# rat.net
KiCad netlist of a schematic drawn in EAGLE
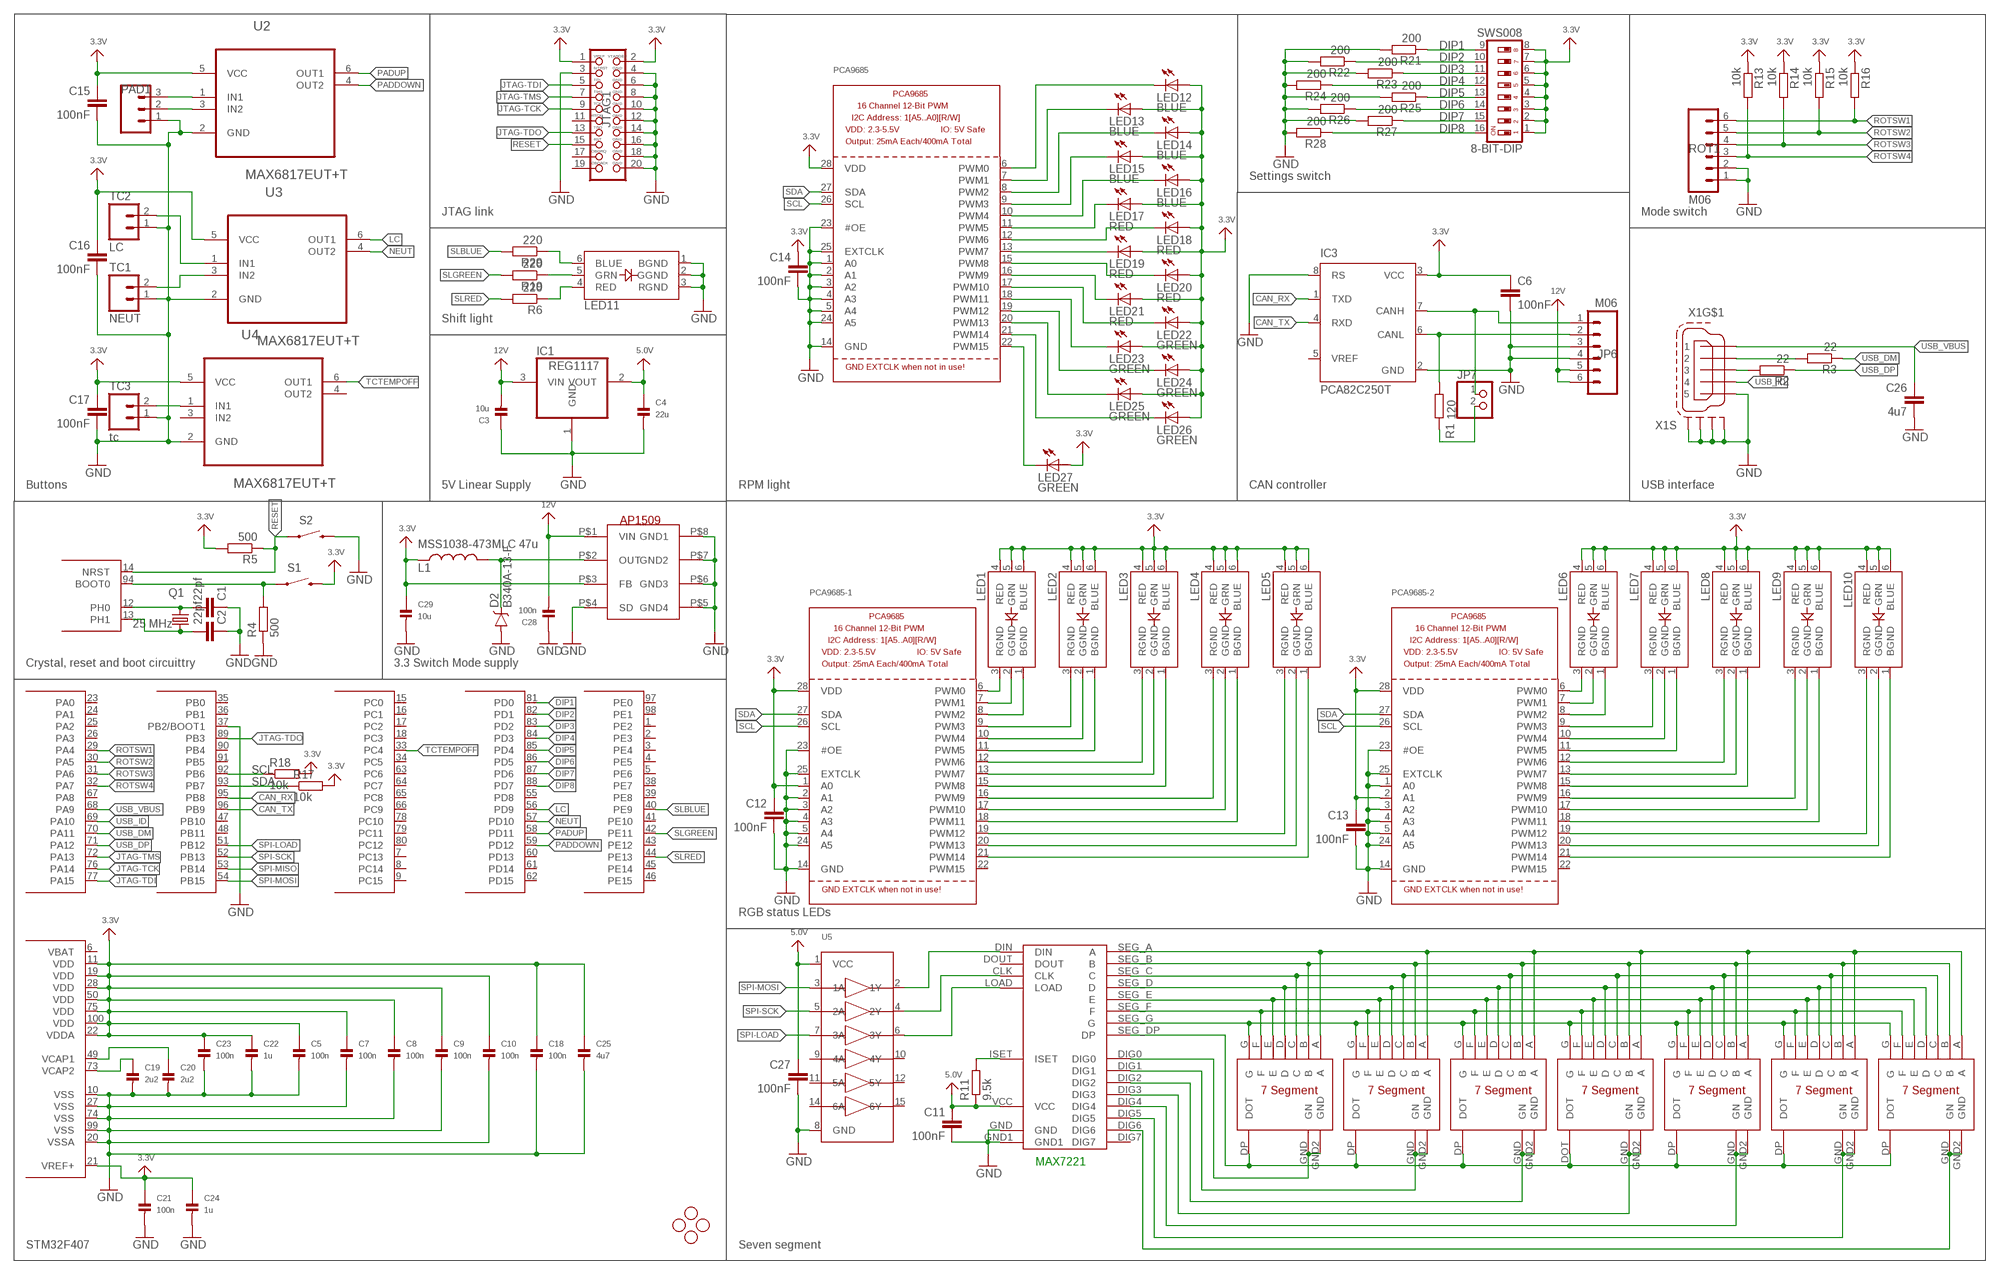
[diagram p0: schematic, sheet 1]

(export (version "E")
  (design (tool "Eeschema 10.0.6"))
  (components
    (comp (ref "8-BIT-DIP")
      (value "SWS008")
      (footprint "eagle-import:SMS-008")
      (libsource (lib "eagle-import") (part "SWS008"))
    )
    (comp (ref "C1")
      (value "22pf")
      (footprint "eagle-import:C0603K")
      (libsource (lib "eagle-import") (part "C-EUC0603K"))
    )
    (comp (ref "C2")
      (value "22pf")
      (footprint "eagle-import:C0603K")
      (libsource (lib "eagle-import") (part "C-EUC0603K"))
    )
    (comp (ref "C3")
      (value "10u")
      (footprint "eagle-import:0805")
      (libsource (lib "eagle-import") (part "CAP_CERAMIC0805"))
    )
    (comp (ref "C4")
      (value "22u")
      (footprint "eagle-import:_0603MP")
      (libsource (lib "eagle-import") (part "CAP_CERAMIC_0603MP"))
    )
    (comp (ref "C5")
      (value "100n")
      (footprint "eagle-import:_0402MP")
      (libsource (lib "eagle-import") (part "CAP_CERAMIC_0402MP"))
    )
    (comp (ref "C6")
      (value "100nF")
      (footprint "eagle-import:C0603K")
      (libsource (lib "eagle-import") (part "C-EUC0603K"))
    )
    (comp (ref "C7")
      (value "100n")
      (footprint "eagle-import:_0402MP")
      (libsource (lib "eagle-import") (part "CAP_CERAMIC_0402MP"))
    )
    (comp (ref "C8")
      (value "100n")
      (footprint "eagle-import:_0402MP")
      (libsource (lib "eagle-import") (part "CAP_CERAMIC_0402MP"))
    )
    (comp (ref "C9")
      (value "100n")
      (footprint "eagle-import:_0402MP")
      (libsource (lib "eagle-import") (part "CAP_CERAMIC_0402MP"))
    )
    (comp (ref "C10")
      (value "100n")
      (footprint "eagle-import:_0402MP")
      (libsource (lib "eagle-import") (part "CAP_CERAMIC_0402MP"))
    )
    (comp (ref "C11")
      (value "100nF")
      (footprint "eagle-import:C0603K")
      (libsource (lib "eagle-import") (part "C-EUC0603K"))
    )
    (comp (ref "C12")
      (value "100nF")
      (footprint "eagle-import:C0603K")
      (libsource (lib "eagle-import") (part "C-EUC0603K"))
    )
    (comp (ref "C13")
      (value "100nF")
      (footprint "eagle-import:C0603K")
      (libsource (lib "eagle-import") (part "C-EUC0603K"))
    )
    (comp (ref "C14")
      (value "100nF")
      (footprint "eagle-import:C0603K")
      (libsource (lib "eagle-import") (part "C-EUC0603K"))
    )
    (comp (ref "C15")
      (value "100nF")
      (footprint "eagle-import:C0603K")
      (libsource (lib "eagle-import") (part "C-EUC0603K"))
    )
    (comp (ref "C16")
      (value "100nF")
      (footprint "eagle-import:C0603K")
      (libsource (lib "eagle-import") (part "C-EUC0603K"))
    )
    (comp (ref "C17")
      (value "100nF")
      (footprint "eagle-import:C0603K")
      (libsource (lib "eagle-import") (part "C-EUC0603K"))
    )
    (comp (ref "C18")
      (value "100n")
      (footprint "eagle-import:_0402MP")
      (libsource (lib "eagle-import") (part "CAP_CERAMIC_0402MP"))
    )
    (comp (ref "C19")
      (value "2u2")
      (footprint "eagle-import:_0402MP")
      (libsource (lib "eagle-import") (part "CAP_CERAMIC_0402MP"))
    )
    (comp (ref "C20")
      (value "2u2")
      (footprint "eagle-import:_0402MP")
      (libsource (lib "eagle-import") (part "CAP_CERAMIC_0402MP"))
    )
    (comp (ref "C21")
      (value "100n")
      (footprint "eagle-import:_0402MP")
      (libsource (lib "eagle-import") (part "CAP_CERAMIC_0402MP"))
    )
    (comp (ref "C22")
      (value "1u")
      (footprint "eagle-import:_0402MP")
      (libsource (lib "eagle-import") (part "CAP_CERAMIC_0402MP"))
    )
    (comp (ref "C23")
      (value "100n")
      (footprint "eagle-import:_0402MP")
      (libsource (lib "eagle-import") (part "CAP_CERAMIC_0402MP"))
    )
    (comp (ref "C24")
      (value "1u")
      (footprint "eagle-import:_0402MP")
      (libsource (lib "eagle-import") (part "CAP_CERAMIC_0402MP"))
    )
    (comp (ref "C25")
      (value "4u7")
      (footprint "eagle-import:_0402MP")
      (libsource (lib "eagle-import") (part "CAP_CERAMIC_0402MP"))
    )
    (comp (ref "C26")
      (value "4u7")
      (footprint "eagle-import:C0603K")
      (libsource (lib "eagle-import") (part "C-EUC0603K"))
    )
    (comp (ref "C27")
      (value "100nF")
      (footprint "eagle-import:C0603K")
      (libsource (lib "eagle-import") (part "C-EUC0603K"))
    )
    (comp (ref "C28")
      (value "100n")
      (footprint "eagle-import:_0603MP")
      (libsource (lib "eagle-import") (part "CAP_CERAMIC_0603MP"))
    )
    (comp (ref "C29")
      (value "10u")
      (footprint "eagle-import:0805")
      (libsource (lib "eagle-import") (part "CAP_CERAMIC0805"))
    )
    (comp (ref "D2")
      (value "B340A-13-F")
      (footprint "eagle-import:SMA-DIODE")
      (libsource (lib "eagle-import") (part "MBRA140"))
    )
    (comp (ref "IC1")
      (value "REG1117")
      (footprint "eagle-import:SOT223")
      (libsource (lib "eagle-import") (part "REG1117"))
    )
    (comp (ref "IC3")
      (value "PCA82C250T")
      (footprint "eagle-import:SO8")
      (libsource (lib "eagle-import") (part "PCA82C250T"))
    )
    (comp (ref "JP2")
      (value "STAND-OFF")
      (footprint "eagle-import:STAND-OFF")
      (libsource (lib "eagle-import") (part "STAND-OFF"))
    )
    (comp (ref "JP3")
      (value "STAND-OFF")
      (footprint "eagle-import:STAND-OFF")
      (libsource (lib "eagle-import") (part "STAND-OFF"))
    )
    (comp (ref "JP4")
      (value "STAND-OFF")
      (footprint "eagle-import:STAND-OFF")
      (libsource (lib "eagle-import") (part "STAND-OFF"))
    )
    (comp (ref "JP5")
      (value "STAND-OFF")
      (footprint "eagle-import:STAND-OFF")
      (libsource (lib "eagle-import") (part "STAND-OFF"))
    )
    (comp (ref "JP6")
      (value "M06")
      (footprint "eagle-import:S6B_PH")
      (libsource (lib "eagle-import") (part "M06"))
    )
    (comp (ref "JP7")
      (value "PINHD-1X2/90")
      (footprint "eagle-import:1X02_90")
      (libsource (lib "eagle-import") (part "PINHD-1X2/90"))
    )
    (comp (ref "JTAG1")
      (value "JTAG-ARMEDGE")
      (footprint "eagle-import:MOLEX20_RIGHTANGLE")
      (libsource (lib "eagle-import") (part "JTAG-ARMEDGE"))
    )
    (comp (ref "L1")
      (value "MSS1038-473MLC 47u")
      (footprint "eagle-import:CDRH125")
      (libsource (lib "eagle-import") (part "INDUCTORPWR"))
    )
    (comp (ref "LED1")
      (value "LED_RGB_PLCC6CREE-CLV6A")
      (footprint "eagle-import:RGBLED_PLCC6")
      (libsource (lib "eagle-import") (part "LED_RGB_PLCC6CREE-CLV6A"))
    )
    (comp (ref "LED2")
      (value "LED_RGB_PLCC6CREE-CLV6A")
      (footprint "eagle-import:RGBLED_PLCC6")
      (libsource (lib "eagle-import") (part "LED_RGB_PLCC6CREE-CLV6A"))
    )
    (comp (ref "LED3")
      (value "LED_RGB_PLCC6CREE-CLV6A")
      (footprint "eagle-import:RGBLED_PLCC6")
      (libsource (lib "eagle-import") (part "LED_RGB_PLCC6CREE-CLV6A"))
    )
    (comp (ref "LED4")
      (value "LED_RGB_PLCC6CREE-CLV6A")
      (footprint "eagle-import:RGBLED_PLCC6")
      (libsource (lib "eagle-import") (part "LED_RGB_PLCC6CREE-CLV6A"))
    )
    (comp (ref "LED5")
      (value "LED_RGB_PLCC6CREE-CLV6A")
      (footprint "eagle-import:RGBLED_PLCC6")
      (libsource (lib "eagle-import") (part "LED_RGB_PLCC6CREE-CLV6A"))
    )
    (comp (ref "LED6")
      (value "LED_RGB_PLCC6CREE-CLV6A")
      (footprint "eagle-import:RGBLED_PLCC6")
      (libsource (lib "eagle-import") (part "LED_RGB_PLCC6CREE-CLV6A"))
    )
    (comp (ref "LED7")
      (value "LED_RGB_PLCC6CREE-CLV6A")
      (footprint "eagle-import:RGBLED_PLCC6")
      (libsource (lib "eagle-import") (part "LED_RGB_PLCC6CREE-CLV6A"))
    )
    (comp (ref "LED8")
      (value "LED_RGB_PLCC6CREE-CLV6A")
      (footprint "eagle-import:RGBLED_PLCC6")
      (libsource (lib "eagle-import") (part "LED_RGB_PLCC6CREE-CLV6A"))
    )
    (comp (ref "LED9")
      (value "LED_RGB_PLCC6CREE-CLV6A")
      (footprint "eagle-import:RGBLED_PLCC6")
      (libsource (lib "eagle-import") (part "LED_RGB_PLCC6CREE-CLV6A"))
    )
    (comp (ref "LED10")
      (value "LED_RGB_PLCC6CREE-CLV6A")
      (footprint "eagle-import:RGBLED_PLCC6")
      (libsource (lib "eagle-import") (part "LED_RGB_PLCC6CREE-CLV6A"))
    )
    (comp (ref "LED11")
      (value "LED_RGB_PLCC6CREE-CLV6A")
      (footprint "eagle-import:RGBLED_PLCC6")
      (libsource (lib "eagle-import") (part "LED_RGB_PLCC6CREE-CLV6A"))
    )
    (comp (ref "LED12")
      (value "BLUE")
      (footprint "eagle-import:1206")
      (libsource (lib "eagle-import") (part "LEDSMT1206"))
    )
    (comp (ref "LED13")
      (value "BLUE")
      (footprint "eagle-import:1206")
      (libsource (lib "eagle-import") (part "LEDSMT1206"))
    )
    (comp (ref "LED14")
      (value "BLUE")
      (footprint "eagle-import:1206")
      (libsource (lib "eagle-import") (part "LEDSMT1206"))
    )
    (comp (ref "LED15")
      (value "BLUE")
      (footprint "eagle-import:1206")
      (libsource (lib "eagle-import") (part "LEDSMT1206"))
    )
    (comp (ref "LED16")
      (value "BLUE")
      (footprint "eagle-import:1206")
      (libsource (lib "eagle-import") (part "LEDSMT1206"))
    )
    (comp (ref "LED17")
      (value "RED")
      (footprint "eagle-import:1206")
      (libsource (lib "eagle-import") (part "LEDSMT1206"))
    )
    (comp (ref "LED18")
      (value "RED")
      (footprint "eagle-import:1206")
      (libsource (lib "eagle-import") (part "LEDSMT1206"))
    )
    (comp (ref "LED19")
      (value "RED")
      (footprint "eagle-import:1206")
      (libsource (lib "eagle-import") (part "LEDSMT1206"))
    )
    (comp (ref "LED20")
      (value "RED")
      (footprint "eagle-import:1206")
      (libsource (lib "eagle-import") (part "LEDSMT1206"))
    )
    (comp (ref "LED21")
      (value "RED")
      (footprint "eagle-import:1206")
      (libsource (lib "eagle-import") (part "LEDSMT1206"))
    )
    (comp (ref "LED22")
      (value "GREEN")
      (footprint "eagle-import:1206")
      (libsource (lib "eagle-import") (part "LEDSMT1206"))
    )
    (comp (ref "LED23")
      (value "GREEN")
      (footprint "eagle-import:1206")
      (libsource (lib "eagle-import") (part "LEDSMT1206"))
    )
    (comp (ref "LED24")
      (value "GREEN")
      (footprint "eagle-import:1206")
      (libsource (lib "eagle-import") (part "LEDSMT1206"))
    )
    (comp (ref "LED25")
      (value "GREEN")
      (footprint "eagle-import:1206")
      (libsource (lib "eagle-import") (part "LEDSMT1206"))
    )
    (comp (ref "LED26")
      (value "GREEN")
      (footprint "eagle-import:1206")
      (libsource (lib "eagle-import") (part "LEDSMT1206"))
    )
    (comp (ref "LED27")
      (value "GREEN")
      (footprint "eagle-import:1206")
      (libsource (lib "eagle-import") (part "LEDSMT1206"))
    )
    (comp (ref "MAX7221")
      (value "MAX7221-SMD")
      (footprint "eagle-import:MAX7221")
      (libsource (lib "eagle-import") (part "MAX7221-SMD"))
    )
    (comp (ref "PAD1")
      (value "M03")
      (footprint "eagle-import:S3B-PH")
      (libsource (lib "eagle-import") (part "M03"))
    )
    (comp (ref "PCA9685")
      (value "PCA9685")
      (footprint "eagle-import:TSSOP28")
      (libsource (lib "eagle-import") (part "PCA9685"))
    )
    (comp (ref "PCA9685-1")
      (value "PCA9685")
      (footprint "eagle-import:TSSOP28")
      (libsource (lib "eagle-import") (part "PCA9685"))
    )
    (comp (ref "PCA9685-2")
      (value "PCA9685")
      (footprint "eagle-import:TSSOP28")
      (libsource (lib "eagle-import") (part "PCA9685"))
    )
    (comp (ref "Q1")
      (value "25 MHz")
      (footprint "eagle-import:HC49U70")
      (libsource (lib "eagle-import") (part "CRYSTALHC49U70"))
    )
    (comp (ref "R1")
      (value "120")
      (footprint "eagle-import:R0603")
      (libsource (lib "eagle-import") (part "resistor_R-EU_R0603"))
    )
    (comp (ref "R2")
      (value "22")
      (footprint "eagle-import:R0603")
      (libsource (lib "eagle-import") (part "R-EU_R0603"))
    )
    (comp (ref "R3")
      (value "22")
      (footprint "eagle-import:R0603")
      (libsource (lib "eagle-import") (part "R-EU_R0603"))
    )
    (comp (ref "R4")
      (value "500")
      (footprint "eagle-import:R0603")
      (libsource (lib "eagle-import") (part "R-EU_R0603"))
    )
    (comp (ref "R5")
      (value "500")
      (footprint "eagle-import:R0603")
      (libsource (lib "eagle-import") (part "R-EU_R0603"))
    )
    (comp (ref "R6")
      (value "220")
      (footprint "eagle-import:R0603")
      (libsource (lib "eagle-import") (part "R-EU_R0603"))
    )
    (comp (ref "R11")
      (value "9.5k")
      (footprint "eagle-import:R0603")
      (libsource (lib "eagle-import") (part "R-EU_R0603"))
    )
    (comp (ref "R13")
      (value "10k")
      (footprint "eagle-import:R0603")
      (libsource (lib "eagle-import") (part "R-EU_R0603"))
    )
    (comp (ref "R14")
      (value "10k")
      (footprint "eagle-import:R0603")
      (libsource (lib "eagle-import") (part "R-EU_R0603"))
    )
    (comp (ref "R15")
      (value "10k")
      (footprint "eagle-import:R0603")
      (libsource (lib "eagle-import") (part "R-EU_R0603"))
    )
    (comp (ref "R16")
      (value "10k")
      (footprint "eagle-import:R0603")
      (libsource (lib "eagle-import") (part "R-EU_R0603"))
    )
    (comp (ref "R17")
      (value "10k")
      (footprint "eagle-import:R0603")
      (libsource (lib "eagle-import") (part "R-EU_R0603"))
    )
    (comp (ref "R18")
      (value "10k")
      (footprint "eagle-import:R0603")
      (libsource (lib "eagle-import") (part "R-EU_R0603"))
    )
    (comp (ref "R19")
      (value "220")
      (footprint "eagle-import:R0603")
      (libsource (lib "eagle-import") (part "R-EU_R0603"))
    )
    (comp (ref "R21")
      (value "200")
      (footprint "eagle-import:R0603")
      (libsource (lib "eagle-import") (part "R-EU_R0603"))
    )
    (comp (ref "R22")
      (value "200")
      (footprint "eagle-import:R0603")
      (libsource (lib "eagle-import") (part "R-EU_R0603"))
    )
    (comp (ref "R23")
      (value "200")
      (footprint "eagle-import:R0603")
      (libsource (lib "eagle-import") (part "R-EU_R0603"))
    )
    (comp (ref "R24")
      (value "200")
      (footprint "eagle-import:R0603")
      (libsource (lib "eagle-import") (part "R-EU_R0603"))
    )
    (comp (ref "R25")
      (value "200")
      (footprint "eagle-import:R0603")
      (libsource (lib "eagle-import") (part "R-EU_R0603"))
    )
    (comp (ref "R26")
      (value "200")
      (footprint "eagle-import:R0603")
      (libsource (lib "eagle-import") (part "R-EU_R0603"))
    )
    (comp (ref "R27")
      (value "200")
      (footprint "eagle-import:R0603")
      (libsource (lib "eagle-import") (part "R-EU_R0603"))
    )
    (comp (ref "R28")
      (value "200")
      (footprint "eagle-import:R0603")
      (libsource (lib "eagle-import") (part "R-EU_R0603"))
    )
    (comp (ref "R29")
      (value "220")
      (footprint "eagle-import:R0603")
      (libsource (lib "eagle-import") (part "R-EU_R0603"))
    )
    (comp (ref "ROT1")
      (value "M06")
      (footprint "eagle-import:S6B_PH")
      (libsource (lib "eagle-import") (part "M06"))
    )
    (comp (ref "S1")
      (value "SWITCH-MOMENTARY-2-SMD-1101NE")
      (footprint "eagle-import:TACTILE-SWITCH-1101NE")
      (libsource (lib "eagle-import") (part "SWITCH-MOMENTARY-2-SMD-1101NE"))
    )
    (comp (ref "S2")
      (value "SWITCH-MOMENTARY-2-SMD-1101NE")
      (footprint "eagle-import:TACTILE-SWITCH-1101NE")
      (libsource (lib "eagle-import") (part "SWITCH-MOMENTARY-2-SMD-1101NE"))
    )
    (comp (ref "TC1")
      (value "NEUT")
      (footprint "eagle-import:S2B-PH")
      (libsource (lib "eagle-import") (part "M02-JST-2MM-SMT"))
    )
    (comp (ref "TC2")
      (value "LC")
      (footprint "eagle-import:S2B-PH")
      (libsource (lib "eagle-import") (part "M02-JST-2MM-SMT"))
    )
    (comp (ref "TC3")
      (value "tc")
      (footprint "eagle-import:S2B-PH")
      (libsource (lib "eagle-import") (part "M02-JST-2MM-SMT"))
    )
    (comp (ref "U$2")
      (value "REDSEVENSEGMENT")
      (footprint "eagle-import:REDSEGMENT")
      (libsource (lib "eagle-import") (part "REDSEVENSEGMENT"))
    )
    (comp (ref "U$3")
      (value "REDSEVENSEGMENT")
      (footprint "eagle-import:REDSEGMENT")
      (libsource (lib "eagle-import") (part "REDSEVENSEGMENT"))
    )
    (comp (ref "U$4")
      (value "REDSEVENSEGMENT")
      (footprint "eagle-import:REDSEGMENT")
      (libsource (lib "eagle-import") (part "REDSEVENSEGMENT"))
    )
    (comp (ref "U$5")
      (value "BIGSEVENSEGMENT")
      (footprint "eagle-import:BIGSEVENSEGMENT")
      (libsource (lib "eagle-import") (part "BIGSEVENSEGMENT"))
    )
    (comp (ref "U$6")
      (value "REDSEVENSEGMENT")
      (footprint "eagle-import:REDSEGMENT")
      (libsource (lib "eagle-import") (part "REDSEVENSEGMENT"))
    )
    (comp (ref "U$7")
      (value "REDSEVENSEGMENT")
      (footprint "eagle-import:REDSEGMENT")
      (libsource (lib "eagle-import") (part "REDSEVENSEGMENT"))
    )
    (comp (ref "U$8")
      (value "REDSEVENSEGMENT")
      (footprint "eagle-import:REDSEGMENT")
      (libsource (lib "eagle-import") (part "REDSEVENSEGMENT"))
    )
    (comp (ref "U$10")
      (value "AP1509")
      (footprint "eagle-import:SOP-8L")
      (libsource (lib "eagle-import") (part "AP1509"))
    )
    (comp (ref "U1")
      (value "STM32F4-100")
      (footprint "eagle-import:SQFP-S-14X14-100")
      (libsource (lib "eagle-import") (part "STM32F4-100"))
    )
    (comp (ref "U2")
      (value "MAX6817EUT+T")
      (footprint "eagle-import:SOT95P280X145-6N")
      (libsource (lib "eagle-import") (part "MAX6817EUT+T"))
    )
    (comp (ref "U3")
      (value "MAX6817EUT+T")
      (footprint "eagle-import:SOT95P280X145-6N")
      (libsource (lib "eagle-import") (part "MAX6817EUT+T"))
    )
    (comp (ref "U4")
      (value "MAX6817EUT+T")
      (footprint "eagle-import:SOT95P280X145-6N")
      (libsource (lib "eagle-import") (part "MAX6817EUT+T"))
    )
    (comp (ref "U5")
      (value "74HC4050D")
      (footprint "eagle-import:SOIC16")
      (libsource (lib "eagle-import") (part "74HC4050D"))
    )
    (comp (ref "X1")
      (value "MINI-USB-SCHIELD-32005-201")
      (footprint "eagle-import:32005-201")
      (libsource (lib "eagle-import") (part "MINI-USB-SCHIELD-32005-201"))
    )
  )
  (nets
    (net (code "1") (name "/VBAT") (class "Default")
      (node (ref "U1") (pin "6") (pinfunction "VBAT_6") (pintype "power_in"))
    )
    (net (code "2") (name "3.3V") (class "Default")
      (node (ref "8-BIT-DIP") (pin "1") (pinfunction "1_1") (pintype "passive"))
      (node (ref "8-BIT-DIP") (pin "2") (pinfunction "2_2") (pintype "passive"))
      (node (ref "8-BIT-DIP") (pin "3") (pinfunction "3_3") (pintype "passive"))
      (node (ref "8-BIT-DIP") (pin "4") (pinfunction "4_4") (pintype "passive"))
      (node (ref "8-BIT-DIP") (pin "5") (pinfunction "5_5") (pintype "passive"))
      (node (ref "8-BIT-DIP") (pin "6") (pinfunction "6_6") (pintype "passive"))
      (node (ref "8-BIT-DIP") (pin "7") (pinfunction "7_7") (pintype "passive"))
      (node (ref "8-BIT-DIP") (pin "8") (pinfunction "8_8") (pintype "passive"))
      (node (ref "C10") (pin "1") (pinfunction "P$1_1") (pintype "passive"))
      (node (ref "C12") (pin "1") (pinfunction "1_1") (pintype "passive"))
      (node (ref "C13") (pin "1") (pinfunction "1_1") (pintype "passive"))
      (node (ref "C14") (pin "1") (pinfunction "1_1") (pintype "passive"))
      (node (ref "C15") (pin "1") (pinfunction "1_1") (pintype "passive"))
      (node (ref "C16") (pin "1") (pinfunction "1_1") (pintype "passive"))
      (node (ref "C17") (pin "1") (pinfunction "1_1") (pintype "passive"))
      (node (ref "C18") (pin "1") (pinfunction "P$1_1") (pintype "passive"))
      (node (ref "C21") (pin "1") (pinfunction "P$1_1") (pintype "passive"))
      (node (ref "C22") (pin "1") (pinfunction "P$1_1") (pintype "passive"))
      (node (ref "C23") (pin "1") (pinfunction "P$1_1") (pintype "passive"))
      (node (ref "C24") (pin "1") (pinfunction "P$1_1") (pintype "passive"))
      (node (ref "C25") (pin "1") (pinfunction "P$1_1") (pintype "passive"))
      (node (ref "C29") (pin "1") (pinfunction "P$1_1") (pintype "passive"))
      (node (ref "C5") (pin "1") (pinfunction "P$1_1") (pintype "passive"))
      (node (ref "C6") (pin "1") (pinfunction "1_1") (pintype "passive"))
      (node (ref "C7") (pin "1") (pinfunction "P$1_1") (pintype "passive"))
      (node (ref "C8") (pin "1") (pinfunction "P$1_1") (pintype "passive"))
      (node (ref "C9") (pin "1") (pinfunction "P$1_1") (pintype "passive"))
      (node (ref "IC3") (pin "3") (pinfunction "VCC_3") (pintype "power_in"))
      (node (ref "JTAG1") (pin "1") (pinfunction "1_1") (pintype "passive"))
      (node (ref "JTAG1") (pin "2") (pinfunction "2_2") (pintype "passive"))
      (node (ref "L1") (pin "1") (pinfunction "1_1") (pintype "passive"))
      (node (ref "LED1") (pin "4") (pinfunction "RED_4") (pintype "bidirectional"))
      (node (ref "LED1") (pin "5") (pinfunction "GRN_5") (pintype "bidirectional"))
      (node (ref "LED1") (pin "6") (pinfunction "BLUE_6") (pintype "bidirectional"))
      (node (ref "LED10") (pin "4") (pinfunction "RED_4") (pintype "bidirectional"))
      (node (ref "LED10") (pin "5") (pinfunction "GRN_5") (pintype "bidirectional"))
      (node (ref "LED10") (pin "6") (pinfunction "BLUE_6") (pintype "bidirectional"))
      (node (ref "LED12") (pin "A") (pinfunction "A_A") (pintype "passive"))
      (node (ref "LED13") (pin "A") (pinfunction "A_A") (pintype "passive"))
      (node (ref "LED14") (pin "A") (pinfunction "A_A") (pintype "passive"))
      (node (ref "LED15") (pin "A") (pinfunction "A_A") (pintype "passive"))
      (node (ref "LED16") (pin "A") (pinfunction "A_A") (pintype "passive"))
      (node (ref "LED17") (pin "A") (pinfunction "A_A") (pintype "passive"))
      (node (ref "LED18") (pin "A") (pinfunction "A_A") (pintype "passive"))
      (node (ref "LED19") (pin "A") (pinfunction "A_A") (pintype "passive"))
      (node (ref "LED2") (pin "4") (pinfunction "RED_4") (pintype "bidirectional"))
      (node (ref "LED2") (pin "5") (pinfunction "GRN_5") (pintype "bidirectional"))
      (node (ref "LED2") (pin "6") (pinfunction "BLUE_6") (pintype "bidirectional"))
      (node (ref "LED20") (pin "A") (pinfunction "A_A") (pintype "passive"))
      (node (ref "LED21") (pin "A") (pinfunction "A_A") (pintype "passive"))
      (node (ref "LED22") (pin "A") (pinfunction "A_A") (pintype "passive"))
      (node (ref "LED23") (pin "A") (pinfunction "A_A") (pintype "passive"))
      (node (ref "LED24") (pin "A") (pinfunction "A_A") (pintype "passive"))
      (node (ref "LED25") (pin "A") (pinfunction "A_A") (pintype "passive"))
      (node (ref "LED26") (pin "A") (pinfunction "A_A") (pintype "passive"))
      (node (ref "LED27") (pin "A") (pinfunction "A_A") (pintype "passive"))
      (node (ref "LED3") (pin "4") (pinfunction "RED_4") (pintype "bidirectional"))
      (node (ref "LED3") (pin "5") (pinfunction "GRN_5") (pintype "bidirectional"))
      (node (ref "LED3") (pin "6") (pinfunction "BLUE_6") (pintype "bidirectional"))
      (node (ref "LED4") (pin "4") (pinfunction "RED_4") (pintype "bidirectional"))
      (node (ref "LED4") (pin "5") (pinfunction "GRN_5") (pintype "bidirectional"))
      (node (ref "LED4") (pin "6") (pinfunction "BLUE_6") (pintype "bidirectional"))
      (node (ref "LED5") (pin "4") (pinfunction "RED_4") (pintype "bidirectional"))
      (node (ref "LED5") (pin "5") (pinfunction "GRN_5") (pintype "bidirectional"))
      (node (ref "LED5") (pin "6") (pinfunction "BLUE_6") (pintype "bidirectional"))
      (node (ref "LED6") (pin "4") (pinfunction "RED_4") (pintype "bidirectional"))
      (node (ref "LED6") (pin "5") (pinfunction "GRN_5") (pintype "bidirectional"))
      (node (ref "LED6") (pin "6") (pinfunction "BLUE_6") (pintype "bidirectional"))
      (node (ref "LED7") (pin "4") (pinfunction "RED_4") (pintype "bidirectional"))
      (node (ref "LED7") (pin "5") (pinfunction "GRN_5") (pintype "bidirectional"))
      (node (ref "LED7") (pin "6") (pinfunction "BLUE_6") (pintype "bidirectional"))
      (node (ref "LED8") (pin "4") (pinfunction "RED_4") (pintype "bidirectional"))
      (node (ref "LED8") (pin "5") (pinfunction "GRN_5") (pintype "bidirectional"))
      (node (ref "LED8") (pin "6") (pinfunction "BLUE_6") (pintype "bidirectional"))
      (node (ref "LED9") (pin "4") (pinfunction "RED_4") (pintype "bidirectional"))
      (node (ref "LED9") (pin "5") (pinfunction "GRN_5") (pintype "bidirectional"))
      (node (ref "LED9") (pin "6") (pinfunction "BLUE_6") (pintype "bidirectional"))
      (node (ref "PCA9685") (pin "28") (pinfunction "VDD_28") (pintype "power_in"))
      (node (ref "PCA9685-1") (pin "1") (pinfunction "A0_1") (pintype "bidirectional"))
      (node (ref "PCA9685-1") (pin "28") (pinfunction "VDD_28") (pintype "power_in"))
      (node (ref "PCA9685-2") (pin "2") (pinfunction "A1_2") (pintype "bidirectional"))
      (node (ref "PCA9685-2") (pin "28") (pinfunction "VDD_28") (pintype "power_in"))
      (node (ref "R13") (pin "1") (pinfunction "1_1") (pintype "passive"))
      (node (ref "R14") (pin "1") (pinfunction "1_1") (pintype "passive"))
      (node (ref "R15") (pin "1") (pinfunction "1_1") (pintype "passive"))
      (node (ref "R16") (pin "1") (pinfunction "1_1") (pintype "passive"))
      (node (ref "R17") (pin "2") (pinfunction "2_2") (pintype "passive"))
      (node (ref "R18") (pin "2") (pinfunction "2_2") (pintype "passive"))
      (node (ref "R5") (pin "2") (pinfunction "2_2") (pintype "passive"))
      (node (ref "S1") (pin "P$2") (pinfunction "2_P$2") (pintype "passive"))
      (node (ref "U$10") (pin "P$3") (pinfunction "FB_P$3") (pintype "bidirectional"))
      (node (ref "U1") (pin "100") (pinfunction "VDD_100") (pintype "power_in"))
      (node (ref "U1") (pin "11") (pinfunction "VDD_11") (pintype "power_in"))
      (node (ref "U1") (pin "19") (pinfunction "VDD_19") (pintype "power_in"))
      (node (ref "U1") (pin "21") (pinfunction "VREF+_21") (pintype "passive"))
      (node (ref "U1") (pin "22") (pinfunction "VDDA_22") (pintype "power_in"))
      (node (ref "U1") (pin "28") (pinfunction "VDD_28") (pintype "power_in"))
      (node (ref "U1") (pin "50") (pinfunction "VDD_50") (pintype "power_in"))
      (node (ref "U1") (pin "75") (pinfunction "VDD_75") (pintype "power_in"))
      (node (ref "U2") (pin "5") (pinfunction "VCC_5") (pintype "power_in"))
      (node (ref "U3") (pin "5") (pinfunction "VCC_5") (pintype "power_in"))
      (node (ref "U4") (pin "5") (pinfunction "VCC_5") (pintype "power_in"))
    )
    (net (code "3") (name "5.0V") (class "Default")
      (node (ref "C11") (pin "1") (pinfunction "1_1") (pintype "passive"))
      (node (ref "C27") (pin "1") (pinfunction "1_1") (pintype "passive"))
      (node (ref "C4") (pin "1") (pinfunction "P$1_1") (pintype "passive"))
      (node (ref "IC1") (pin "2") (pinfunction "VOUT_2") (pintype "output"))
      (node (ref "MAX7221") (pin "VCC") (pinfunction "VCC_VCC") (pintype "bidirectional"))
      (node (ref "R11") (pin "1") (pinfunction "1_1") (pintype "passive"))
      (node (ref "U5") (pin "1") (pinfunction "VCC_1") (pintype "bidirectional"))
    )
    (net (code "4") (name "12V") (class "Default")
      (node (ref "C28") (pin "2") (pinfunction "P$2_2") (pintype "passive"))
      (node (ref "C3") (pin "2") (pinfunction "P$2_2") (pintype "passive"))
      (node (ref "IC1") (pin "3") (pinfunction "VIN_3") (pintype "input"))
      (node (ref "JP6") (pin "5") (pinfunction "5_5") (pintype "passive"))
      (node (ref "JP6") (pin "6") (pinfunction "6_6") (pintype "passive"))
      (node (ref "U$10") (pin "P$1") (pinfunction "VIN_P$1") (pintype "bidirectional"))
    )
    (net (code "5") (name "CAN_RX") (class "Default")
      (node (ref "IC3") (pin "1") (pinfunction "TXD_1") (pintype "input"))
      (node (ref "U1") (pin "95") (pinfunction "PB8_95") (pintype "bidirectional"))
    )
    (net (code "6") (name "CAN_TX") (class "Default")
      (node (ref "IC3") (pin "4") (pinfunction "RXD_4") (pintype "output"))
      (node (ref "U1") (pin "96") (pinfunction "PB9_96") (pintype "bidirectional"))
    )
    (net (code "7") (name "DIP1") (class "Default")
      (node (ref "8-BIT-DIP") (pin "9") (pinfunction "9_9") (pintype "passive"))
      (node (ref "R21") (pin "1") (pinfunction "1_1") (pintype "passive"))
      (node (ref "U1") (pin "81") (pinfunction "PD0_81") (pintype "bidirectional"))
    )
    (net (code "8") (name "DIP2") (class "Default")
      (node (ref "8-BIT-DIP") (pin "10") (pinfunction "10_10") (pintype "passive"))
      (node (ref "R22") (pin "1") (pinfunction "1_1") (pintype "passive"))
      (node (ref "U1") (pin "82") (pinfunction "PD1_82") (pintype "bidirectional"))
    )
    (net (code "9") (name "DIP3") (class "Default")
      (node (ref "8-BIT-DIP") (pin "11") (pinfunction "11_11") (pintype "passive"))
      (node (ref "R23") (pin "1") (pinfunction "1_1") (pintype "passive"))
      (node (ref "U1") (pin "83") (pinfunction "PD2_83") (pintype "bidirectional"))
    )
    (net (code "10") (name "DIP4") (class "Default")
      (node (ref "8-BIT-DIP") (pin "12") (pinfunction "12_12") (pintype "passive"))
      (node (ref "R24") (pin "1") (pinfunction "1_1") (pintype "passive"))
      (node (ref "U1") (pin "84") (pinfunction "PD3_84") (pintype "bidirectional"))
    )
    (net (code "11") (name "DIP5") (class "Default")
      (node (ref "8-BIT-DIP") (pin "13") (pinfunction "13_13") (pintype "passive"))
      (node (ref "R25") (pin "1") (pinfunction "1_1") (pintype "passive"))
      (node (ref "U1") (pin "85") (pinfunction "PD4_85") (pintype "bidirectional"))
    )
    (net (code "12") (name "DIP6") (class "Default")
      (node (ref "8-BIT-DIP") (pin "14") (pinfunction "14_14") (pintype "passive"))
      (node (ref "R26") (pin "1") (pinfunction "1_1") (pintype "passive"))
      (node (ref "U1") (pin "86") (pinfunction "PD5_86") (pintype "bidirectional"))
    )
    (net (code "13") (name "DIP7") (class "Default")
      (node (ref "8-BIT-DIP") (pin "15") (pinfunction "15_15") (pintype "passive"))
      (node (ref "R27") (pin "1") (pinfunction "1_1") (pintype "passive"))
      (node (ref "U1") (pin "87") (pinfunction "PD6_87") (pintype "bidirectional"))
    )
    (net (code "14") (name "DIP8") (class "Default")
      (node (ref "8-BIT-DIP") (pin "16") (pinfunction "16_16") (pintype "passive"))
      (node (ref "R28") (pin "1") (pinfunction "1_1") (pintype "passive"))
      (node (ref "U1") (pin "88") (pinfunction "PD7_88") (pintype "bidirectional"))
    )
    (net (code "15") (name "GND") (class "Default")
      (node (ref "C1") (pin "1") (pinfunction "1_1") (pintype "passive"))
      (node (ref "C10") (pin "2") (pinfunction "P$2_2") (pintype "passive"))
      (node (ref "C11") (pin "2") (pinfunction "2_2") (pintype "passive"))
      (node (ref "C12") (pin "2") (pinfunction "2_2") (pintype "passive"))
      (node (ref "C13") (pin "2") (pinfunction "2_2") (pintype "passive"))
      (node (ref "C14") (pin "2") (pinfunction "2_2") (pintype "passive"))
      (node (ref "C15") (pin "2") (pinfunction "2_2") (pintype "passive"))
      (node (ref "C16") (pin "2") (pinfunction "2_2") (pintype "passive"))
      (node (ref "C17") (pin "2") (pinfunction "2_2") (pintype "passive"))
      (node (ref "C18") (pin "2") (pinfunction "P$2_2") (pintype "passive"))
      (node (ref "C19") (pin "2") (pinfunction "P$2_2") (pintype "passive"))
      (node (ref "C2") (pin "1") (pinfunction "1_1") (pintype "passive"))
      (node (ref "C20") (pin "2") (pinfunction "P$2_2") (pintype "passive"))
      (node (ref "C21") (pin "2") (pinfunction "P$2_2") (pintype "passive"))
      (node (ref "C22") (pin "2") (pinfunction "P$2_2") (pintype "passive"))
      (node (ref "C23") (pin "2") (pinfunction "P$2_2") (pintype "passive"))
      (node (ref "C24") (pin "2") (pinfunction "P$2_2") (pintype "passive"))
      (node (ref "C25") (pin "2") (pinfunction "P$2_2") (pintype "passive"))
      (node (ref "C26") (pin "2") (pinfunction "2_2") (pintype "passive"))
      (node (ref "C27") (pin "2") (pinfunction "2_2") (pintype "passive"))
      (node (ref "C28") (pin "1") (pinfunction "P$1_1") (pintype "passive"))
      (node (ref "C29") (pin "2") (pinfunction "P$2_2") (pintype "passive"))
      (node (ref "C3") (pin "1") (pinfunction "P$1_1") (pintype "passive"))
      (node (ref "C4") (pin "2") (pinfunction "P$2_2") (pintype "passive"))
      (node (ref "C5") (pin "2") (pinfunction "P$2_2") (pintype "passive"))
      (node (ref "C6") (pin "2") (pinfunction "2_2") (pintype "passive"))
      (node (ref "C7") (pin "2") (pinfunction "P$2_2") (pintype "passive"))
      (node (ref "C8") (pin "2") (pinfunction "P$2_2") (pintype "passive"))
      (node (ref "C9") (pin "2") (pinfunction "P$2_2") (pintype "passive"))
      (node (ref "D2") (pin "A") (pinfunction "A_A") (pintype "passive"))
      (node (ref "IC1") (pin "1") (pinfunction "GND_1") (pintype "power_in"))
      (node (ref "IC3") (pin "2") (pinfunction "GND_2") (pintype "power_in"))
      (node (ref "IC3") (pin "8") (pinfunction "RS_8") (pintype "input"))
      (node (ref "JP6") (pin "3") (pinfunction "3_3") (pintype "passive"))
      (node (ref "JP6") (pin "4") (pinfunction "4_4") (pintype "passive"))
      (node (ref "JTAG1") (pin "10") (pinfunction "10_10") (pintype "passive"))
      (node (ref "JTAG1") (pin "12") (pinfunction "12_12") (pintype "passive"))
      (node (ref "JTAG1") (pin "14") (pinfunction "14_14") (pintype "passive"))
      (node (ref "JTAG1") (pin "16") (pinfunction "16_16") (pintype "passive"))
      (node (ref "JTAG1") (pin "18") (pinfunction "18_18") (pintype "passive"))
      (node (ref "JTAG1") (pin "20") (pinfunction "20_20") (pintype "passive"))
      (node (ref "JTAG1") (pin "3") (pinfunction "3_3") (pintype "passive"))
      (node (ref "JTAG1") (pin "4") (pinfunction "4_4") (pintype "passive"))
      (node (ref "JTAG1") (pin "6") (pinfunction "6_6") (pintype "passive"))
      (node (ref "JTAG1") (pin "8") (pinfunction "8_8") (pintype "passive"))
      (node (ref "LED11") (pin "1") (pinfunction "BGND_1") (pintype "power_in"))
      (node (ref "LED11") (pin "2") (pinfunction "GGND_2") (pintype "power_in"))
      (node (ref "LED11") (pin "3") (pinfunction "RGND_3") (pintype "power_in"))
      (node (ref "MAX7221") (pin "GND") (pinfunction "GND_GND") (pintype "bidirectional"))
      (node (ref "MAX7221") (pin "GND1") (pinfunction "GND1_GND1") (pintype "bidirectional"))
      (node (ref "PAD1") (pin "1") (pinfunction "1_1") (pintype "passive"))
      (node (ref "PCA9685") (pin "1") (pinfunction "A0_1") (pintype "bidirectional"))
      (node (ref "PCA9685") (pin "14") (pinfunction "GND_14") (pintype "power_in"))
      (node (ref "PCA9685") (pin "2") (pinfunction "A1_2") (pintype "bidirectional"))
      (node (ref "PCA9685") (pin "23") (pinfunction "#OE_23") (pintype "input"))
      (node (ref "PCA9685") (pin "24") (pinfunction "A5_24") (pintype "bidirectional"))
      (node (ref "PCA9685") (pin "25") (pinfunction "EXTCLK_25") (pintype "input"))
      (node (ref "PCA9685") (pin "3") (pinfunction "A2_3") (pintype "bidirectional"))
      (node (ref "PCA9685") (pin "4") (pinfunction "A3_4") (pintype "bidirectional"))
      (node (ref "PCA9685") (pin "5") (pinfunction "A4_5") (pintype "bidirectional"))
      (node (ref "PCA9685-1") (pin "14") (pinfunction "GND_14") (pintype "power_in"))
      (node (ref "PCA9685-1") (pin "2") (pinfunction "A1_2") (pintype "bidirectional"))
      (node (ref "PCA9685-1") (pin "23") (pinfunction "#OE_23") (pintype "input"))
      (node (ref "PCA9685-1") (pin "24") (pinfunction "A5_24") (pintype "bidirectional"))
      (node (ref "PCA9685-1") (pin "25") (pinfunction "EXTCLK_25") (pintype "input"))
      (node (ref "PCA9685-1") (pin "3") (pinfunction "A2_3") (pintype "bidirectional"))
      (node (ref "PCA9685-1") (pin "4") (pinfunction "A3_4") (pintype "bidirectional"))
      (node (ref "PCA9685-1") (pin "5") (pinfunction "A4_5") (pintype "bidirectional"))
      (node (ref "PCA9685-2") (pin "1") (pinfunction "A0_1") (pintype "bidirectional"))
      (node (ref "PCA9685-2") (pin "14") (pinfunction "GND_14") (pintype "power_in"))
      (node (ref "PCA9685-2") (pin "23") (pinfunction "#OE_23") (pintype "input"))
      (node (ref "PCA9685-2") (pin "24") (pinfunction "A5_24") (pintype "bidirectional"))
      (node (ref "PCA9685-2") (pin "25") (pinfunction "EXTCLK_25") (pintype "input"))
      (node (ref "PCA9685-2") (pin "3") (pinfunction "A2_3") (pintype "bidirectional"))
      (node (ref "PCA9685-2") (pin "4") (pinfunction "A3_4") (pintype "bidirectional"))
      (node (ref "PCA9685-2") (pin "5") (pinfunction "A4_5") (pintype "bidirectional"))
      (node (ref "R21") (pin "2") (pinfunction "2_2") (pintype "passive"))
      (node (ref "R22") (pin "2") (pinfunction "2_2") (pintype "passive"))
      (node (ref "R23") (pin "2") (pinfunction "2_2") (pintype "passive"))
      (node (ref "R24") (pin "2") (pinfunction "2_2") (pintype "passive"))
      (node (ref "R25") (pin "2") (pinfunction "2_2") (pintype "passive"))
      (node (ref "R26") (pin "2") (pinfunction "2_2") (pintype "passive"))
      (node (ref "R27") (pin "2") (pinfunction "2_2") (pintype "passive"))
      (node (ref "R28") (pin "2") (pinfunction "2_2") (pintype "passive"))
      (node (ref "R4") (pin "1") (pinfunction "1_1") (pintype "passive"))
      (node (ref "ROT1") (pin "1") (pinfunction "1_1") (pintype "passive"))
      (node (ref "ROT1") (pin "2") (pinfunction "2_2") (pintype "passive"))
      (node (ref "S2") (pin "P$2") (pinfunction "2_P$2") (pintype "passive"))
      (node (ref "TC1") (pin "1") (pinfunction "1_1") (pintype "passive"))
      (node (ref "TC2") (pin "1") (pinfunction "1_1") (pintype "passive"))
      (node (ref "TC3") (pin "1") (pinfunction "1_1") (pintype "passive"))
      (node (ref "U$10") (pin "P$4") (pinfunction "SD_P$4") (pintype "bidirectional"))
      (node (ref "U$10") (pin "P$5") (pinfunction "GND4_P$5") (pintype "bidirectional"))
      (node (ref "U$10") (pin "P$6") (pinfunction "GND3_P$6") (pintype "bidirectional"))
      (node (ref "U$10") (pin "P$7") (pinfunction "GND2_P$7") (pintype "bidirectional"))
      (node (ref "U$10") (pin "P$8") (pinfunction "GND1_P$8") (pintype "bidirectional"))
      (node (ref "U1") (pin "10") (pinfunction "VSS_10") (pintype "power_in"))
      (node (ref "U1") (pin "20") (pinfunction "VSSA_20") (pintype "power_in"))
      (node (ref "U1") (pin "27") (pinfunction "VSS_27") (pintype "power_in"))
      (node (ref "U1") (pin "37") (pinfunction "PB2/BOOT1_37") (pintype "bidirectional"))
      (node (ref "U1") (pin "74") (pinfunction "VSS_74") (pintype "power_in"))
      (node (ref "U1") (pin "99") (pinfunction "VSS_99") (pintype "power_in"))
      (node (ref "U2") (pin "2") (pinfunction "GND_2") (pintype "passive"))
      (node (ref "U3") (pin "2") (pinfunction "GND_2") (pintype "passive"))
      (node (ref "U4") (pin "2") (pinfunction "GND_2") (pintype "passive"))
      (node (ref "U5") (pin "8") (pinfunction "GND_8") (pintype "bidirectional"))
      (node (ref "X1") (pin "5") (pinfunction "5_5") (pintype "passive"))
      (node (ref "X1") (pin "M1") (pinfunction "S1_M1") (pintype "passive"))
      (node (ref "X1") (pin "M2") (pinfunction "S2_M2") (pintype "passive"))
      (node (ref "X1") (pin "M3") (pinfunction "S3_M3") (pintype "passive"))
      (node (ref "X1") (pin "M4") (pinfunction "S4_M4") (pintype "passive"))
    )
    (net (code "16") (name "JTAG-TCK") (class "Default")
      (node (ref "JTAG1") (pin "9") (pinfunction "9_9") (pintype "passive"))
      (node (ref "U1") (pin "76") (pinfunction "PA14_76") (pintype "bidirectional"))
    )
    (net (code "17") (name "JTAG-TDI") (class "Default")
      (node (ref "JTAG1") (pin "5") (pinfunction "5_5") (pintype "passive"))
      (node (ref "U1") (pin "77") (pinfunction "PA15_77") (pintype "bidirectional"))
    )
    (net (code "18") (name "JTAG-TDO") (class "Default")
      (node (ref "JTAG1") (pin "13") (pinfunction "13_13") (pintype "passive"))
      (node (ref "U1") (pin "89") (pinfunction "PB3_89") (pintype "bidirectional"))
    )
    (net (code "19") (name "JTAG-TMS") (class "Default")
      (node (ref "JTAG1") (pin "7") (pinfunction "7_7") (pintype "passive"))
      (node (ref "U1") (pin "72") (pinfunction "PA13_72") (pintype "bidirectional"))
    )
    (net (code "20") (name "LC") (class "Default")
      (node (ref "U1") (pin "56") (pinfunction "PD9_56") (pintype "bidirectional"))
      (node (ref "U3") (pin "6") (pinfunction "OUT1_6") (pintype "output"))
    )
    (net (code "21") (name "NEUT") (class "Default")
      (node (ref "U1") (pin "57") (pinfunction "PD10_57") (pintype "bidirectional"))
      (node (ref "U3") (pin "4") (pinfunction "OUT2_4") (pintype "output"))
    )
    (net (code "22") (name "Net-(C19-P$1)") (class "Default")
      (node (ref "C19") (pin "1") (pinfunction "P$1_1") (pintype "passive"))
      (node (ref "U1") (pin "73") (pinfunction "VCAP2_73") (pintype "passive"))
    )
    (net (code "23") (name "Net-(C20-P$1)") (class "Default")
      (node (ref "C20") (pin "1") (pinfunction "P$1_1") (pintype "passive"))
      (node (ref "U1") (pin "49") (pinfunction "VCAP1_49") (pintype "passive"))
    )
    (net (code "24") (name "Net-(IC3-CANH)") (class "Default")
      (node (ref "IC3") (pin "7") (pinfunction "CANH_7") (pintype "bidirectional"))
      (node (ref "JP6") (pin "1") (pinfunction "1_1") (pintype "passive"))
      (node (ref "JP7") (pin "1") (pinfunction "1_1") (pintype "passive"))
    )
    (net (code "25") (name "Net-(IC3-CANL)") (class "Default")
      (node (ref "IC3") (pin "6") (pinfunction "CANL_6") (pintype "bidirectional"))
      (node (ref "JP6") (pin "2") (pinfunction "2_2") (pintype "passive"))
      (node (ref "R1") (pin "1") (pinfunction "1_1") (pintype "passive"))
    )
    (net (code "26") (name "Net-(JP7-Pad2)") (class "Default")
      (node (ref "JP7") (pin "2") (pinfunction "2_2") (pintype "passive"))
      (node (ref "R1") (pin "2") (pinfunction "2_2") (pintype "passive"))
    )
    (net (code "27") (name "Net-(LED1-BGND)") (class "Default")
      (node (ref "LED1") (pin "1") (pinfunction "BGND_1") (pintype "power_in"))
      (node (ref "PCA9685-1") (pin "8") (pinfunction "PWM2_8") (pintype "output"))
    )
    (net (code "28") (name "Net-(LED1-GGND)") (class "Default")
      (node (ref "LED1") (pin "2") (pinfunction "GGND_2") (pintype "power_in"))
      (node (ref "PCA9685-1") (pin "7") (pinfunction "PWM1_7") (pintype "output"))
    )
    (net (code "29") (name "Net-(LED1-RGND)") (class "Default")
      (node (ref "LED1") (pin "3") (pinfunction "RGND_3") (pintype "power_in"))
      (node (ref "PCA9685-1") (pin "6") (pinfunction "PWM0_6") (pintype "output"))
    )
    (net (code "30") (name "Net-(LED2-BGND)") (class "Default")
      (node (ref "LED2") (pin "1") (pinfunction "BGND_1") (pintype "power_in"))
      (node (ref "PCA9685-1") (pin "11") (pinfunction "PWM5_11") (pintype "output"))
    )
    (net (code "31") (name "Net-(LED2-GGND)") (class "Default")
      (node (ref "LED2") (pin "2") (pinfunction "GGND_2") (pintype "power_in"))
      (node (ref "PCA9685-1") (pin "10") (pinfunction "PWM4_10") (pintype "output"))
    )
    (net (code "32") (name "Net-(LED2-RGND)") (class "Default")
      (node (ref "LED2") (pin "3") (pinfunction "RGND_3") (pintype "power_in"))
      (node (ref "PCA9685-1") (pin "9") (pinfunction "PWM3_9") (pintype "output"))
    )
    (net (code "33") (name "Net-(LED3-BGND)") (class "Default")
      (node (ref "LED3") (pin "1") (pinfunction "BGND_1") (pintype "power_in"))
      (node (ref "PCA9685-1") (pin "15") (pinfunction "PWM8_15") (pintype "output"))
    )
    (net (code "34") (name "Net-(LED3-GGND)") (class "Default")
      (node (ref "LED3") (pin "2") (pinfunction "GGND_2") (pintype "power_in"))
      (node (ref "PCA9685-1") (pin "13") (pinfunction "PWM7_13") (pintype "output"))
    )
    (net (code "35") (name "Net-(LED3-RGND)") (class "Default")
      (node (ref "LED3") (pin "3") (pinfunction "RGND_3") (pintype "power_in"))
      (node (ref "PCA9685-1") (pin "12") (pinfunction "PWM6_12") (pintype "output"))
    )
    (net (code "36") (name "Net-(LED4-BGND)") (class "Default")
      (node (ref "LED4") (pin "1") (pinfunction "BGND_1") (pintype "power_in"))
      (node (ref "PCA9685-1") (pin "18") (pinfunction "PWM11_18") (pintype "output"))
    )
    (net (code "37") (name "Net-(LED4-GGND)") (class "Default")
      (node (ref "LED4") (pin "2") (pinfunction "GGND_2") (pintype "power_in"))
      (node (ref "PCA9685-1") (pin "17") (pinfunction "PWM10_17") (pintype "output"))
    )
    (net (code "38") (name "Net-(LED4-RGND)") (class "Default")
      (node (ref "LED4") (pin "3") (pinfunction "RGND_3") (pintype "power_in"))
      (node (ref "PCA9685-1") (pin "16") (pinfunction "PWM9_16") (pintype "output"))
    )
    (net (code "39") (name "Net-(LED5-BGND)") (class "Default")
      (node (ref "LED5") (pin "1") (pinfunction "BGND_1") (pintype "power_in"))
      (node (ref "PCA9685-1") (pin "21") (pinfunction "PWM14_21") (pintype "output"))
    )
    (net (code "40") (name "Net-(LED5-GGND)") (class "Default")
      (node (ref "LED5") (pin "2") (pinfunction "GGND_2") (pintype "power_in"))
      (node (ref "PCA9685-1") (pin "20") (pinfunction "PWM13_20") (pintype "output"))
    )
    (net (code "41") (name "Net-(LED5-RGND)") (class "Default")
      (node (ref "LED5") (pin "3") (pinfunction "RGND_3") (pintype "power_in"))
      (node (ref "PCA9685-1") (pin "19") (pinfunction "PWM12_19") (pintype "output"))
    )
    (net (code "42") (name "Net-(LED6-BGND)") (class "Default")
      (node (ref "LED6") (pin "1") (pinfunction "BGND_1") (pintype "power_in"))
      (node (ref "PCA9685-2") (pin "8") (pinfunction "PWM2_8") (pintype "output"))
    )
    (net (code "43") (name "Net-(LED6-GGND)") (class "Default")
      (node (ref "LED6") (pin "2") (pinfunction "GGND_2") (pintype "power_in"))
      (node (ref "PCA9685-2") (pin "7") (pinfunction "PWM1_7") (pintype "output"))
    )
    (net (code "44") (name "Net-(LED6-RGND)") (class "Default")
      (node (ref "LED6") (pin "3") (pinfunction "RGND_3") (pintype "power_in"))
      (node (ref "PCA9685-2") (pin "6") (pinfunction "PWM0_6") (pintype "output"))
    )
    (net (code "45") (name "Net-(LED7-BGND)") (class "Default")
      (node (ref "LED7") (pin "1") (pinfunction "BGND_1") (pintype "power_in"))
      (node (ref "PCA9685-2") (pin "11") (pinfunction "PWM5_11") (pintype "output"))
    )
    (net (code "46") (name "Net-(LED7-GGND)") (class "Default")
      (node (ref "LED7") (pin "2") (pinfunction "GGND_2") (pintype "power_in"))
      (node (ref "PCA9685-2") (pin "10") (pinfunction "PWM4_10") (pintype "output"))
    )
    (net (code "47") (name "Net-(LED7-RGND)") (class "Default")
      (node (ref "LED7") (pin "3") (pinfunction "RGND_3") (pintype "power_in"))
      (node (ref "PCA9685-2") (pin "9") (pinfunction "PWM3_9") (pintype "output"))
    )
    (net (code "48") (name "Net-(LED8-BGND)") (class "Default")
      (node (ref "LED8") (pin "1") (pinfunction "BGND_1") (pintype "power_in"))
      (node (ref "PCA9685-2") (pin "15") (pinfunction "PWM8_15") (pintype "output"))
    )
    (net (code "49") (name "Net-(LED8-GGND)") (class "Default")
      (node (ref "LED8") (pin "2") (pinfunction "GGND_2") (pintype "power_in"))
      (node (ref "PCA9685-2") (pin "13") (pinfunction "PWM7_13") (pintype "output"))
    )
    (net (code "50") (name "Net-(LED8-RGND)") (class "Default")
      (node (ref "LED8") (pin "3") (pinfunction "RGND_3") (pintype "power_in"))
      (node (ref "PCA9685-2") (pin "12") (pinfunction "PWM6_12") (pintype "output"))
    )
    (net (code "51") (name "Net-(LED9-BGND)") (class "Default")
      (node (ref "LED9") (pin "1") (pinfunction "BGND_1") (pintype "power_in"))
      (node (ref "PCA9685-2") (pin "18") (pinfunction "PWM11_18") (pintype "output"))
    )
    (net (code "52") (name "Net-(LED9-GGND)") (class "Default")
      (node (ref "LED9") (pin "2") (pinfunction "GGND_2") (pintype "power_in"))
      (node (ref "PCA9685-2") (pin "17") (pinfunction "PWM10_17") (pintype "output"))
    )
    (net (code "53") (name "Net-(LED9-RGND)") (class "Default")
      (node (ref "LED9") (pin "3") (pinfunction "RGND_3") (pintype "power_in"))
      (node (ref "PCA9685-2") (pin "16") (pinfunction "PWM9_16") (pintype "output"))
    )
    (net (code "54") (name "Net-(LED10-BGND)") (class "Default")
      (node (ref "LED10") (pin "1") (pinfunction "BGND_1") (pintype "power_in"))
      (node (ref "PCA9685-2") (pin "21") (pinfunction "PWM14_21") (pintype "output"))
    )
    (net (code "55") (name "Net-(LED10-GGND)") (class "Default")
      (node (ref "LED10") (pin "2") (pinfunction "GGND_2") (pintype "power_in"))
      (node (ref "PCA9685-2") (pin "20") (pinfunction "PWM13_20") (pintype "output"))
    )
    (net (code "56") (name "Net-(LED10-RGND)") (class "Default")
      (node (ref "LED10") (pin "3") (pinfunction "RGND_3") (pintype "power_in"))
      (node (ref "PCA9685-2") (pin "19") (pinfunction "PWM12_19") (pintype "output"))
    )
    (net (code "57") (name "Net-(LED11-BLUE)") (class "Default")
      (node (ref "LED11") (pin "6") (pinfunction "BLUE_6") (pintype "bidirectional"))
      (node (ref "R29") (pin "1") (pinfunction "1_1") (pintype "passive"))
    )
    (net (code "58") (name "Net-(LED11-GRN)") (class "Default")
      (node (ref "LED11") (pin "5") (pinfunction "GRN_5") (pintype "bidirectional"))
      (node (ref "R19") (pin "1") (pinfunction "1_1") (pintype "passive"))
    )
    (net (code "59") (name "Net-(LED11-RED)") (class "Default")
      (node (ref "LED11") (pin "4") (pinfunction "RED_4") (pintype "bidirectional"))
      (node (ref "R6") (pin "1") (pinfunction "1_1") (pintype "passive"))
    )
    (net (code "60") (name "Net-(MAX7221-A)") (class "Default")
      (node (ref "MAX7221") (pin "SEG_A") (pinfunction "A_SEG_A") (pintype "bidirectional"))
      (node (ref "U$2") (pin "A") (pinfunction "A_A") (pintype "bidirectional"))
      (node (ref "U$3") (pin "A") (pinfunction "A_A") (pintype "bidirectional"))
      (node (ref "U$4") (pin "A") (pinfunction "A_A") (pintype "bidirectional"))
      (node (ref "U$5") (pin "A") (pinfunction "A_A") (pintype "bidirectional"))
      (node (ref "U$6") (pin "A") (pinfunction "A_A") (pintype "bidirectional"))
      (node (ref "U$7") (pin "A") (pinfunction "A_A") (pintype "bidirectional"))
      (node (ref "U$8") (pin "A") (pinfunction "A_A") (pintype "bidirectional"))
    )
    (net (code "61") (name "Net-(MAX7221-B)") (class "Default")
      (node (ref "MAX7221") (pin "SEG_B") (pinfunction "B_SEG_B") (pintype "bidirectional"))
      (node (ref "U$2") (pin "B") (pinfunction "B_B") (pintype "bidirectional"))
      (node (ref "U$3") (pin "B") (pinfunction "B_B") (pintype "bidirectional"))
      (node (ref "U$4") (pin "B") (pinfunction "B_B") (pintype "bidirectional"))
      (node (ref "U$5") (pin "B") (pinfunction "B_B") (pintype "bidirectional"))
      (node (ref "U$6") (pin "B") (pinfunction "B_B") (pintype "bidirectional"))
      (node (ref "U$7") (pin "B") (pinfunction "B_B") (pintype "bidirectional"))
      (node (ref "U$8") (pin "B") (pinfunction "B_B") (pintype "bidirectional"))
    )
    (net (code "62") (name "Net-(MAX7221-C)") (class "Default")
      (node (ref "MAX7221") (pin "SEG_C") (pinfunction "C_SEG_C") (pintype "bidirectional"))
      (node (ref "U$2") (pin "C") (pinfunction "C_C") (pintype "bidirectional"))
      (node (ref "U$3") (pin "C") (pinfunction "C_C") (pintype "bidirectional"))
      (node (ref "U$4") (pin "C") (pinfunction "C_C") (pintype "bidirectional"))
      (node (ref "U$5") (pin "C") (pinfunction "C_C") (pintype "bidirectional"))
      (node (ref "U$6") (pin "C") (pinfunction "C_C") (pintype "bidirectional"))
      (node (ref "U$7") (pin "C") (pinfunction "C_C") (pintype "bidirectional"))
      (node (ref "U$8") (pin "C") (pinfunction "C_C") (pintype "bidirectional"))
    )
    (net (code "63") (name "Net-(MAX7221-D)") (class "Default")
      (node (ref "MAX7221") (pin "SEG_D") (pinfunction "D_SEG_D") (pintype "bidirectional"))
      (node (ref "U$2") (pin "D") (pinfunction "D_D") (pintype "bidirectional"))
      (node (ref "U$3") (pin "D") (pinfunction "D_D") (pintype "bidirectional"))
      (node (ref "U$4") (pin "D") (pinfunction "D_D") (pintype "bidirectional"))
      (node (ref "U$5") (pin "D") (pinfunction "D_D") (pintype "bidirectional"))
      (node (ref "U$6") (pin "D") (pinfunction "D_D") (pintype "bidirectional"))
      (node (ref "U$7") (pin "D") (pinfunction "D_D") (pintype "bidirectional"))
      (node (ref "U$8") (pin "D") (pinfunction "D_D") (pintype "bidirectional"))
    )
    (net (code "64") (name "Net-(MAX7221-DP)") (class "Default")
      (node (ref "MAX7221") (pin "SEG_DP") (pinfunction "DP_SEG_DP") (pintype "bidirectional"))
      (node (ref "U$2") (pin "DP") (pinfunction "DOT_DP") (pintype "bidirectional"))
      (node (ref "U$3") (pin "DP") (pinfunction "DOT_DP") (pintype "bidirectional"))
      (node (ref "U$4") (pin "DP") (pinfunction "DOT_DP") (pintype "bidirectional"))
      (node (ref "U$5") (pin "DOT") (pinfunction "DOT_DOT") (pintype "bidirectional"))
      (node (ref "U$6") (pin "DP") (pinfunction "DOT_DP") (pintype "bidirectional"))
      (node (ref "U$7") (pin "DP") (pinfunction "DOT_DP") (pintype "bidirectional"))
      (node (ref "U$8") (pin "DP") (pinfunction "DOT_DP") (pintype "bidirectional"))
    )
    (net (code "65") (name "Net-(MAX7221-E)") (class "Default")
      (node (ref "MAX7221") (pin "SEG_E") (pinfunction "E_SEG_E") (pintype "bidirectional"))
      (node (ref "U$2") (pin "E") (pinfunction "E_E") (pintype "bidirectional"))
      (node (ref "U$3") (pin "E") (pinfunction "E_E") (pintype "bidirectional"))
      (node (ref "U$4") (pin "E") (pinfunction "E_E") (pintype "bidirectional"))
      (node (ref "U$5") (pin "E") (pinfunction "E_E") (pintype "bidirectional"))
      (node (ref "U$6") (pin "E") (pinfunction "E_E") (pintype "bidirectional"))
      (node (ref "U$7") (pin "E") (pinfunction "E_E") (pintype "bidirectional"))
      (node (ref "U$8") (pin "E") (pinfunction "E_E") (pintype "bidirectional"))
    )
    (net (code "66") (name "Net-(MAX7221-F)") (class "Default")
      (node (ref "MAX7221") (pin "SEG_F") (pinfunction "F_SEG_F") (pintype "bidirectional"))
      (node (ref "U$2") (pin "F") (pinfunction "F_F") (pintype "bidirectional"))
      (node (ref "U$3") (pin "F") (pinfunction "F_F") (pintype "bidirectional"))
      (node (ref "U$4") (pin "F") (pinfunction "F_F") (pintype "bidirectional"))
      (node (ref "U$5") (pin "F") (pinfunction "F_F") (pintype "bidirectional"))
      (node (ref "U$6") (pin "F") (pinfunction "F_F") (pintype "bidirectional"))
      (node (ref "U$7") (pin "F") (pinfunction "F_F") (pintype "bidirectional"))
      (node (ref "U$8") (pin "F") (pinfunction "F_F") (pintype "bidirectional"))
    )
    (net (code "67") (name "Net-(MAX7221-G)") (class "Default")
      (node (ref "MAX7221") (pin "SEG_G") (pinfunction "G_SEG_G") (pintype "bidirectional"))
      (node (ref "U$2") (pin "G") (pinfunction "G_G") (pintype "bidirectional"))
      (node (ref "U$3") (pin "G") (pinfunction "G_G") (pintype "bidirectional"))
      (node (ref "U$4") (pin "G") (pinfunction "G_G") (pintype "bidirectional"))
      (node (ref "U$5") (pin "G") (pinfunction "G_G") (pintype "bidirectional"))
      (node (ref "U$6") (pin "G") (pinfunction "G_G") (pintype "bidirectional"))
      (node (ref "U$7") (pin "G") (pinfunction "G_G") (pintype "bidirectional"))
      (node (ref "U$8") (pin "G") (pinfunction "G_G") (pintype "bidirectional"))
    )
    (net (code "68") (name "Net-(MAX7221-PadISET)") (class "Default")
      (node (ref "MAX7221") (pin "ISET") (pinfunction "ISET_ISET") (pintype "bidirectional"))
      (node (ref "R11") (pin "2") (pinfunction "2_2") (pintype "passive"))
    )
    (net (code "69") (name "Net-(PCA9685-PWM0)") (class "Default")
      (node (ref "LED12") (pin "C") (pinfunction "C_C") (pintype "passive"))
      (node (ref "PCA9685") (pin "6") (pinfunction "PWM0_6") (pintype "output"))
    )
    (net (code "70") (name "Net-(PCA9685-PWM1)") (class "Default")
      (node (ref "LED13") (pin "C") (pinfunction "C_C") (pintype "passive"))
      (node (ref "PCA9685") (pin "7") (pinfunction "PWM1_7") (pintype "output"))
    )
    (net (code "71") (name "Net-(PCA9685-PWM2)") (class "Default")
      (node (ref "LED14") (pin "C") (pinfunction "C_C") (pintype "passive"))
      (node (ref "PCA9685") (pin "8") (pinfunction "PWM2_8") (pintype "output"))
    )
    (net (code "72") (name "Net-(PCA9685-PWM3)") (class "Default")
      (node (ref "LED15") (pin "C") (pinfunction "C_C") (pintype "passive"))
      (node (ref "PCA9685") (pin "9") (pinfunction "PWM3_9") (pintype "output"))
    )
    (net (code "73") (name "Net-(PCA9685-PWM4)") (class "Default")
      (node (ref "LED16") (pin "C") (pinfunction "C_C") (pintype "passive"))
      (node (ref "PCA9685") (pin "10") (pinfunction "PWM4_10") (pintype "output"))
    )
    (net (code "74") (name "Net-(PCA9685-PWM5)") (class "Default")
      (node (ref "LED17") (pin "C") (pinfunction "C_C") (pintype "passive"))
      (node (ref "PCA9685") (pin "11") (pinfunction "PWM5_11") (pintype "output"))
    )
    (net (code "75") (name "Net-(PCA9685-PWM6)") (class "Default")
      (node (ref "LED18") (pin "C") (pinfunction "C_C") (pintype "passive"))
      (node (ref "PCA9685") (pin "12") (pinfunction "PWM6_12") (pintype "output"))
    )
    (net (code "76") (name "Net-(PCA9685-PWM7)") (class "Default")
      (node (ref "LED19") (pin "C") (pinfunction "C_C") (pintype "passive"))
      (node (ref "PCA9685") (pin "13") (pinfunction "PWM7_13") (pintype "output"))
    )
    (net (code "77") (name "Net-(PCA9685-PWM8)") (class "Default")
      (node (ref "LED20") (pin "C") (pinfunction "C_C") (pintype "passive"))
      (node (ref "PCA9685") (pin "15") (pinfunction "PWM8_15") (pintype "output"))
    )
    (net (code "78") (name "Net-(PCA9685-PWM9)") (class "Default")
      (node (ref "LED21") (pin "C") (pinfunction "C_C") (pintype "passive"))
      (node (ref "PCA9685") (pin "16") (pinfunction "PWM9_16") (pintype "output"))
    )
    (net (code "79") (name "Net-(PCA9685-PWM10)") (class "Default")
      (node (ref "LED22") (pin "C") (pinfunction "C_C") (pintype "passive"))
      (node (ref "PCA9685") (pin "17") (pinfunction "PWM10_17") (pintype "output"))
    )
    (net (code "80") (name "Net-(PCA9685-PWM11)") (class "Default")
      (node (ref "LED23") (pin "C") (pinfunction "C_C") (pintype "passive"))
      (node (ref "PCA9685") (pin "18") (pinfunction "PWM11_18") (pintype "output"))
    )
    (net (code "81") (name "Net-(PCA9685-PWM12)") (class "Default")
      (node (ref "LED24") (pin "C") (pinfunction "C_C") (pintype "passive"))
      (node (ref "PCA9685") (pin "19") (pinfunction "PWM12_19") (pintype "output"))
    )
    (net (code "82") (name "Net-(PCA9685-PWM13)") (class "Default")
      (node (ref "LED25") (pin "C") (pinfunction "C_C") (pintype "passive"))
      (node (ref "PCA9685") (pin "20") (pinfunction "PWM13_20") (pintype "output"))
    )
    (net (code "83") (name "Net-(PCA9685-PWM14)") (class "Default")
      (node (ref "LED26") (pin "C") (pinfunction "C_C") (pintype "passive"))
      (node (ref "PCA9685") (pin "21") (pinfunction "PWM14_21") (pintype "output"))
    )
    (net (code "84") (name "Net-(PCA9685-PWM15)") (class "Default")
      (node (ref "LED27") (pin "C") (pinfunction "C_C") (pintype "passive"))
      (node (ref "PCA9685") (pin "22") (pinfunction "PWM15_22") (pintype "output"))
    )
    (net (code "85") (name "Net-(R2-Pad2)") (class "Default")
      (node (ref "R2") (pin "2") (pinfunction "2_2") (pintype "passive"))
      (node (ref "X1") (pin "3") (pinfunction "3_3") (pintype "passive"))
    )
    (net (code "86") (name "Net-(R3-Pad2)") (class "Default")
      (node (ref "R3") (pin "2") (pinfunction "2_2") (pintype "passive"))
      (node (ref "X1") (pin "2") (pinfunction "2_2") (pintype "passive"))
    )
    (net (code "87") (name "Net-(S1-1)") (class "Default")
      (node (ref "R4") (pin "2") (pinfunction "2_2") (pintype "passive"))
      (node (ref "S1") (pin "P$1") (pinfunction "1_P$1") (pintype "passive"))
      (node (ref "U1") (pin "94") (pinfunction "BOOT0_94") (pintype "bidirectional"))
    )
    (net (code "88") (name "Net-(U$2-GN)") (class "Default")
      (node (ref "MAX7221") (pin "DIG0") (pinfunction "DIG0_DIG0") (pintype "bidirectional"))
      (node (ref "U$2") (pin "GND") (pinfunction "GN_GND") (pintype "bidirectional"))
      (node (ref "U$2") (pin "GND2") (pinfunction "GND_GND2") (pintype "bidirectional"))
    )
    (net (code "89") (name "Net-(U$3-GN)") (class "Default")
      (node (ref "MAX7221") (pin "DIG1") (pinfunction "DIG1_DIG1") (pintype "bidirectional"))
      (node (ref "U$3") (pin "GND") (pinfunction "GN_GND") (pintype "bidirectional"))
      (node (ref "U$3") (pin "GND2") (pinfunction "GND_GND2") (pintype "bidirectional"))
    )
    (net (code "90") (name "Net-(U$4-GN)") (class "Default")
      (node (ref "MAX7221") (pin "DIG2") (pinfunction "DIG2_DIG2") (pintype "bidirectional"))
      (node (ref "U$4") (pin "GND") (pinfunction "GN_GND") (pintype "bidirectional"))
      (node (ref "U$4") (pin "GND2") (pinfunction "GND_GND2") (pintype "bidirectional"))
    )
    (net (code "91") (name "Net-(U$5-GN)") (class "Default")
      (node (ref "MAX7221") (pin "DIG3") (pinfunction "DIG3_DIG3") (pintype "bidirectional"))
      (node (ref "U$5") (pin "GND") (pinfunction "GN_GND") (pintype "bidirectional"))
      (node (ref "U$5") (pin "GND2") (pinfunction "GND_GND2") (pintype "bidirectional"))
    )
    (net (code "92") (name "Net-(U$6-GN)") (class "Default")
      (node (ref "MAX7221") (pin "DIG4") (pinfunction "DIG4_DIG4") (pintype "bidirectional"))
      (node (ref "U$6") (pin "GND") (pinfunction "GN_GND") (pintype "bidirectional"))
      (node (ref "U$6") (pin "GND2") (pinfunction "GND_GND2") (pintype "bidirectional"))
    )
    (net (code "93") (name "Net-(U$7-GN)") (class "Default")
      (node (ref "MAX7221") (pin "DIG5") (pinfunction "DIG5_DIG5") (pintype "bidirectional"))
      (node (ref "U$7") (pin "GND") (pinfunction "GN_GND") (pintype "bidirectional"))
      (node (ref "U$7") (pin "GND2") (pinfunction "GND_GND2") (pintype "bidirectional"))
    )
    (net (code "94") (name "Net-(U$8-GN)") (class "Default")
      (node (ref "MAX7221") (pin "DIG6") (pinfunction "DIG6_DIG6") (pintype "bidirectional"))
      (node (ref "U$8") (pin "GND") (pinfunction "GN_GND") (pintype "bidirectional"))
      (node (ref "U$8") (pin "GND2") (pinfunction "GND_GND2") (pintype "bidirectional"))
    )
    (net (code "95") (name "Net-(U$10-OUT)") (class "Default")
      (node (ref "D2") (pin "C") (pinfunction "C_C") (pintype "passive"))
      (node (ref "L1") (pin "2") (pinfunction "2_2") (pintype "passive"))
      (node (ref "U$10") (pin "P$2") (pinfunction "OUT_P$2") (pintype "bidirectional"))
    )
    (net (code "96") (name "Net-(U1G-PH0)") (class "Default")
      (node (ref "C1") (pin "2") (pinfunction "2_2") (pintype "passive"))
      (node (ref "Q1") (pin "2") (pinfunction "2_2") (pintype "passive"))
      (node (ref "U1") (pin "12") (pinfunction "PH0_12") (pintype "bidirectional"))
    )
    (net (code "97") (name "Net-(U1G-PH1)") (class "Default")
      (node (ref "C2") (pin "2") (pinfunction "2_2") (pintype "passive"))
      (node (ref "Q1") (pin "1") (pinfunction "1_1") (pintype "passive"))
      (node (ref "U1") (pin "13") (pinfunction "PH1_13") (pintype "bidirectional"))
    )
    (net (code "98") (name "Net-(U2-IN1)") (class "Default")
      (node (ref "PAD1") (pin "3") (pinfunction "3_3") (pintype "passive"))
      (node (ref "U2") (pin "1") (pinfunction "IN1_1") (pintype "input"))
    )
    (net (code "99") (name "Net-(U2-IN2)") (class "Default")
      (node (ref "PAD1") (pin "2") (pinfunction "2_2") (pintype "passive"))
      (node (ref "U2") (pin "3") (pinfunction "IN2_3") (pintype "input"))
    )
    (net (code "100") (name "Net-(U3-IN1)") (class "Default")
      (node (ref "TC2") (pin "2") (pinfunction "2_2") (pintype "passive"))
      (node (ref "U3") (pin "1") (pinfunction "IN1_1") (pintype "input"))
    )
    (net (code "101") (name "Net-(U3-IN2)") (class "Default")
      (node (ref "TC1") (pin "2") (pinfunction "2_2") (pintype "passive"))
      (node (ref "U3") (pin "3") (pinfunction "IN2_3") (pintype "input"))
    )
    (net (code "102") (name "Net-(U4-IN1)") (class "Default")
      (node (ref "TC3") (pin "2") (pinfunction "2_2") (pintype "passive"))
      (node (ref "U4") (pin "1") (pinfunction "IN1_1") (pintype "input"))
    )
    (net (code "103") (name "Net-(U5-1Y)") (class "Default")
      (node (ref "MAX7221") (pin "DIN") (pinfunction "DIN_DIN") (pintype "bidirectional"))
      (node (ref "U5") (pin "2") (pinfunction "1Y_2") (pintype "bidirectional"))
    )
    (net (code "104") (name "Net-(U5-2Y)") (class "Default")
      (node (ref "MAX7221") (pin "CLK") (pinfunction "CLK_CLK") (pintype "bidirectional"))
      (node (ref "U5") (pin "4") (pinfunction "2Y_4") (pintype "bidirectional"))
    )
    (net (code "105") (name "Net-(U5-3Y)") (class "Default")
      (node (ref "MAX7221") (pin "LOAD") (pinfunction "LOAD_LOAD") (pintype "bidirectional"))
      (node (ref "U5") (pin "6") (pinfunction "3Y_6") (pintype "bidirectional"))
    )
    (net (code "106") (name "PADDOWN") (class "Default")
      (node (ref "U1") (pin "59") (pinfunction "PD12_59") (pintype "bidirectional"))
      (node (ref "U2") (pin "4") (pinfunction "OUT2_4") (pintype "output"))
    )
    (net (code "107") (name "PADUP") (class "Default")
      (node (ref "U1") (pin "58") (pinfunction "PD11_58") (pintype "bidirectional"))
      (node (ref "U2") (pin "6") (pinfunction "OUT1_6") (pintype "output"))
    )
    (net (code "108") (name "RESET") (class "Default")
      (node (ref "JTAG1") (pin "15") (pinfunction "15_15") (pintype "passive"))
      (node (ref "R5") (pin "1") (pinfunction "1_1") (pintype "passive"))
      (node (ref "S2") (pin "P$1") (pinfunction "1_P$1") (pintype "passive"))
      (node (ref "U1") (pin "14") (pinfunction "NRST_14") (pintype "bidirectional"))
    )
    (net (code "109") (name "ROTSW1") (class "Default")
      (node (ref "R16") (pin "2") (pinfunction "2_2") (pintype "passive"))
      (node (ref "ROT1") (pin "6") (pinfunction "6_6") (pintype "passive"))
      (node (ref "U1") (pin "29") (pinfunction "PA4_29") (pintype "bidirectional"))
    )
    (net (code "110") (name "ROTSW2") (class "Default")
      (node (ref "R15") (pin "2") (pinfunction "2_2") (pintype "passive"))
      (node (ref "ROT1") (pin "5") (pinfunction "5_5") (pintype "passive"))
      (node (ref "U1") (pin "30") (pinfunction "PA5_30") (pintype "bidirectional"))
    )
    (net (code "111") (name "ROTSW3") (class "Default")
      (node (ref "R14") (pin "2") (pinfunction "2_2") (pintype "passive"))
      (node (ref "ROT1") (pin "4") (pinfunction "4_4") (pintype "passive"))
      (node (ref "U1") (pin "31") (pinfunction "PA6_31") (pintype "bidirectional"))
    )
    (net (code "112") (name "ROTSW4") (class "Default")
      (node (ref "R13") (pin "2") (pinfunction "2_2") (pintype "passive"))
      (node (ref "ROT1") (pin "3") (pinfunction "3_3") (pintype "passive"))
      (node (ref "U1") (pin "32") (pinfunction "PA7_32") (pintype "bidirectional"))
    )
    (net (code "113") (name "SCL") (class "Default")
      (node (ref "PCA9685") (pin "26") (pinfunction "SCL_26") (pintype "bidirectional"))
      (node (ref "PCA9685-1") (pin "26") (pinfunction "SCL_26") (pintype "bidirectional"))
      (node (ref "PCA9685-2") (pin "26") (pinfunction "SCL_26") (pintype "bidirectional"))
      (node (ref "R18") (pin "1") (pinfunction "1_1") (pintype "passive"))
      (node (ref "U1") (pin "92") (pinfunction "PB6_92") (pintype "bidirectional"))
    )
    (net (code "114") (name "SDA") (class "Default")
      (node (ref "PCA9685") (pin "27") (pinfunction "SDA_27") (pintype "bidirectional"))
      (node (ref "PCA9685-1") (pin "27") (pinfunction "SDA_27") (pintype "bidirectional"))
      (node (ref "PCA9685-2") (pin "27") (pinfunction "SDA_27") (pintype "bidirectional"))
      (node (ref "R17") (pin "1") (pinfunction "1_1") (pintype "passive"))
      (node (ref "U1") (pin "93") (pinfunction "PB7_93") (pintype "bidirectional"))
    )
    (net (code "115") (name "SLBLUE") (class "Default")
      (node (ref "R29") (pin "2") (pinfunction "2_2") (pintype "passive"))
      (node (ref "U1") (pin "40") (pinfunction "PE9_40") (pintype "bidirectional"))
    )
    (net (code "116") (name "SLGREEN") (class "Default")
      (node (ref "R19") (pin "2") (pinfunction "2_2") (pintype "passive"))
      (node (ref "U1") (pin "42") (pinfunction "PE11_42") (pintype "bidirectional"))
    )
    (net (code "117") (name "SLRED") (class "Default")
      (node (ref "R6") (pin "2") (pinfunction "2_2") (pintype "passive"))
      (node (ref "U1") (pin "44") (pinfunction "PE13_44") (pintype "bidirectional"))
    )
    (net (code "118") (name "SPI-LOAD") (class "Default")
      (node (ref "U1") (pin "51") (pinfunction "PB12_51") (pintype "bidirectional"))
      (node (ref "U5") (pin "7") (pinfunction "3A_7") (pintype "bidirectional"))
    )
    (net (code "119") (name "SPI-MISO") (class "Default")
      (node (ref "U1") (pin "53") (pinfunction "PB14_53") (pintype "bidirectional"))
    )
    (net (code "120") (name "SPI-MOSI") (class "Default")
      (node (ref "U1") (pin "54") (pinfunction "PB15_54") (pintype "bidirectional"))
      (node (ref "U5") (pin "3") (pinfunction "1A_3") (pintype "bidirectional"))
    )
    (net (code "121") (name "SPI-SCK") (class "Default")
      (node (ref "U1") (pin "52") (pinfunction "PB13_52") (pintype "bidirectional"))
      (node (ref "U5") (pin "5") (pinfunction "2A_5") (pintype "bidirectional"))
    )
    (net (code "122") (name "TCTEMPOFF") (class "Default")
      (node (ref "U1") (pin "33") (pinfunction "PC4_33") (pintype "bidirectional"))
      (node (ref "U4") (pin "6") (pinfunction "OUT1_6") (pintype "output"))
    )
    (net (code "123") (name "USB_DM") (class "Default")
      (node (ref "R3") (pin "1") (pinfunction "1_1") (pintype "passive"))
      (node (ref "U1") (pin "70") (pinfunction "PA11_70") (pintype "bidirectional"))
    )
    (net (code "124") (name "USB_DP") (class "Default")
      (node (ref "R2") (pin "1") (pinfunction "1_1") (pintype "passive"))
      (node (ref "U1") (pin "71") (pinfunction "PA12_71") (pintype "bidirectional"))
    )
    (net (code "125") (name "USB_ID") (class "Default")
      (node (ref "U1") (pin "69") (pinfunction "PA10_69") (pintype "bidirectional"))
      (node (ref "X1") (pin "4") (pinfunction "4_4") (pintype "passive"))
    )
    (net (code "126") (name "USB_VBUS") (class "Default")
      (node (ref "C26") (pin "1") (pinfunction "1_1") (pintype "passive"))
      (node (ref "U1") (pin "68") (pinfunction "PA9_68") (pintype "bidirectional"))
      (node (ref "X1") (pin "1") (pinfunction "1_1") (pintype "passive"))
    )
    (net (code "127") (name "unconnected-(IC3-VREF-Pad5)") (class "Default")
      (node (ref "IC3") (pin "5") (pinfunction "VREF_5") (pintype "output"))
    )
    (net (code "128") (name "unconnected-(JTAG1-Pad11)") (class "Default")
      (node (ref "JTAG1") (pin "11") (pinfunction "11_11") (pintype "passive"))
    )
    (net (code "129") (name "unconnected-(JTAG1-Pad17)") (class "Default")
      (node (ref "JTAG1") (pin "17") (pinfunction "17_17") (pintype "passive"))
    )
    (net (code "130") (name "unconnected-(JTAG1-Pad19)") (class "Default")
      (node (ref "JTAG1") (pin "19") (pinfunction "19_19") (pintype "passive"))
    )
    (net (code "131") (name "unconnected-(MAX7221-PadDIG7)") (class "Default")
      (node (ref "MAX7221") (pin "DIG7") (pinfunction "DIG7_DIG7") (pintype "bidirectional"))
    )
    (net (code "132") (name "unconnected-(MAX7221-PadDOUT)") (class "Default")
      (node (ref "MAX7221") (pin "DOUT") (pinfunction "DOUT_DOUT") (pintype "bidirectional"))
    )
    (net (code "133") (name "unconnected-(PCA9685-1-PWM15-Pad22)") (class "Default")
      (node (ref "PCA9685-1") (pin "22") (pinfunction "PWM15_22") (pintype "output"))
    )
    (net (code "134") (name "unconnected-(PCA9685-2-PWM15-Pad22)") (class "Default")
      (node (ref "PCA9685-2") (pin "22") (pinfunction "PWM15_22") (pintype "output"))
    )
    (net (code "135") (name "unconnected-(U1B-PA0-Pad23)") (class "Default")
      (node (ref "U1") (pin "23") (pinfunction "PA0_23") (pintype "bidirectional"))
    )
    (net (code "136") (name "unconnected-(U1B-PA1-Pad24)") (class "Default")
      (node (ref "U1") (pin "24") (pinfunction "PA1_24") (pintype "bidirectional"))
    )
    (net (code "137") (name "unconnected-(U1B-PA2-Pad25)") (class "Default")
      (node (ref "U1") (pin "25") (pinfunction "PA2_25") (pintype "bidirectional"))
    )
    (net (code "138") (name "unconnected-(U1B-PA3-Pad26)") (class "Default")
      (node (ref "U1") (pin "26") (pinfunction "PA3_26") (pintype "bidirectional"))
    )
    (net (code "139") (name "unconnected-(U1B-PA8-Pad67)") (class "Default")
      (node (ref "U1") (pin "67") (pinfunction "PA8_67") (pintype "bidirectional"))
    )
    (net (code "140") (name "unconnected-(U1C-PB0-Pad35)") (class "Default")
      (node (ref "U1") (pin "35") (pinfunction "PB0_35") (pintype "bidirectional"))
    )
    (net (code "141") (name "unconnected-(U1C-PB1-Pad36)") (class "Default")
      (node (ref "U1") (pin "36") (pinfunction "PB1_36") (pintype "bidirectional"))
    )
    (net (code "142") (name "unconnected-(U1C-PB4-Pad90)") (class "Default")
      (node (ref "U1") (pin "90") (pinfunction "PB4_90") (pintype "bidirectional"))
    )
    (net (code "143") (name "unconnected-(U1C-PB5-Pad91)") (class "Default")
      (node (ref "U1") (pin "91") (pinfunction "PB5_91") (pintype "bidirectional"))
    )
    (net (code "144") (name "unconnected-(U1C-PB10-Pad47)") (class "Default")
      (node (ref "U1") (pin "47") (pinfunction "PB10_47") (pintype "bidirectional"))
    )
    (net (code "145") (name "unconnected-(U1C-PB11-Pad48)") (class "Default")
      (node (ref "U1") (pin "48") (pinfunction "PB11_48") (pintype "bidirectional"))
    )
    (net (code "146") (name "unconnected-(U1D-PC0-Pad15)") (class "Default")
      (node (ref "U1") (pin "15") (pinfunction "PC0_15") (pintype "bidirectional"))
    )
    (net (code "147") (name "unconnected-(U1D-PC1-Pad16)") (class "Default")
      (node (ref "U1") (pin "16") (pinfunction "PC1_16") (pintype "bidirectional"))
    )
    (net (code "148") (name "unconnected-(U1D-PC2-Pad17)") (class "Default")
      (node (ref "U1") (pin "17") (pinfunction "PC2_17") (pintype "bidirectional"))
    )
    (net (code "149") (name "unconnected-(U1D-PC3-Pad18)") (class "Default")
      (node (ref "U1") (pin "18") (pinfunction "PC3_18") (pintype "bidirectional"))
    )
    (net (code "150") (name "unconnected-(U1D-PC5-Pad34)") (class "Default")
      (node (ref "U1") (pin "34") (pinfunction "PC5_34") (pintype "bidirectional"))
    )
    (net (code "151") (name "unconnected-(U1D-PC6-Pad63)") (class "Default")
      (node (ref "U1") (pin "63") (pinfunction "PC6_63") (pintype "bidirectional"))
    )
    (net (code "152") (name "unconnected-(U1D-PC7-Pad64)") (class "Default")
      (node (ref "U1") (pin "64") (pinfunction "PC7_64") (pintype "bidirectional"))
    )
    (net (code "153") (name "unconnected-(U1D-PC8-Pad65)") (class "Default")
      (node (ref "U1") (pin "65") (pinfunction "PC8_65") (pintype "bidirectional"))
    )
    (net (code "154") (name "unconnected-(U1D-PC9-Pad66)") (class "Default")
      (node (ref "U1") (pin "66") (pinfunction "PC9_66") (pintype "bidirectional"))
    )
    (net (code "155") (name "unconnected-(U1D-PC10-Pad78)") (class "Default")
      (node (ref "U1") (pin "78") (pinfunction "PC10_78") (pintype "bidirectional"))
    )
    (net (code "156") (name "unconnected-(U1D-PC11-Pad79)") (class "Default")
      (node (ref "U1") (pin "79") (pinfunction "PC11_79") (pintype "bidirectional"))
    )
    (net (code "157") (name "unconnected-(U1D-PC12-Pad80)") (class "Default")
      (node (ref "U1") (pin "80") (pinfunction "PC12_80") (pintype "bidirectional"))
    )
    (net (code "158") (name "unconnected-(U1D-PC13-Pad7)") (class "Default")
      (node (ref "U1") (pin "7") (pinfunction "PC13_7") (pintype "bidirectional"))
    )
    (net (code "159") (name "unconnected-(U1D-PC14-Pad8)") (class "Default")
      (node (ref "U1") (pin "8") (pinfunction "PC14_8") (pintype "bidirectional"))
    )
    (net (code "160") (name "unconnected-(U1D-PC15-Pad9)") (class "Default")
      (node (ref "U1") (pin "9") (pinfunction "PC15_9") (pintype "bidirectional"))
    )
    (net (code "161") (name "unconnected-(U1E-PD8-Pad55)") (class "Default")
      (node (ref "U1") (pin "55") (pinfunction "PD8_55") (pintype "bidirectional"))
    )
    (net (code "162") (name "unconnected-(U1E-PD13-Pad60)") (class "Default")
      (node (ref "U1") (pin "60") (pinfunction "PD13_60") (pintype "bidirectional"))
    )
    (net (code "163") (name "unconnected-(U1E-PD14-Pad61)") (class "Default")
      (node (ref "U1") (pin "61") (pinfunction "PD14_61") (pintype "bidirectional"))
    )
    (net (code "164") (name "unconnected-(U1E-PD15-Pad62)") (class "Default")
      (node (ref "U1") (pin "62") (pinfunction "PD15_62") (pintype "bidirectional"))
    )
    (net (code "165") (name "unconnected-(U1F-PE0-Pad97)") (class "Default")
      (node (ref "U1") (pin "97") (pinfunction "PE0_97") (pintype "bidirectional"))
    )
    (net (code "166") (name "unconnected-(U1F-PE1-Pad98)") (class "Default")
      (node (ref "U1") (pin "98") (pinfunction "PE1_98") (pintype "bidirectional"))
    )
    (net (code "167") (name "unconnected-(U1F-PE2-Pad1)") (class "Default")
      (node (ref "U1") (pin "1") (pinfunction "PE2_1") (pintype "bidirectional"))
    )
    (net (code "168") (name "unconnected-(U1F-PE3-Pad2)") (class "Default")
      (node (ref "U1") (pin "2") (pinfunction "PE3_2") (pintype "bidirectional"))
    )
    (net (code "169") (name "unconnected-(U1F-PE4-Pad3)") (class "Default")
      (node (ref "U1") (pin "3") (pinfunction "PE4_3") (pintype "bidirectional"))
    )
    (net (code "170") (name "unconnected-(U1F-PE5-Pad4)") (class "Default")
      (node (ref "U1") (pin "4") (pinfunction "PE5_4") (pintype "bidirectional"))
    )
    (net (code "171") (name "unconnected-(U1F-PE6-Pad5)") (class "Default")
      (node (ref "U1") (pin "5") (pinfunction "PE6_5") (pintype "bidirectional"))
    )
    (net (code "172") (name "unconnected-(U1F-PE7-Pad38)") (class "Default")
      (node (ref "U1") (pin "38") (pinfunction "PE7_38") (pintype "bidirectional"))
    )
    (net (code "173") (name "unconnected-(U1F-PE8-Pad39)") (class "Default")
      (node (ref "U1") (pin "39") (pinfunction "PE8_39") (pintype "bidirectional"))
    )
    (net (code "174") (name "unconnected-(U1F-PE10-Pad41)") (class "Default")
      (node (ref "U1") (pin "41") (pinfunction "PE10_41") (pintype "bidirectional"))
    )
    (net (code "175") (name "unconnected-(U1F-PE12-Pad43)") (class "Default")
      (node (ref "U1") (pin "43") (pinfunction "PE12_43") (pintype "bidirectional"))
    )
    (net (code "176") (name "unconnected-(U1F-PE14-Pad45)") (class "Default")
      (node (ref "U1") (pin "45") (pinfunction "PE14_45") (pintype "bidirectional"))
    )
    (net (code "177") (name "unconnected-(U1F-PE15-Pad46)") (class "Default")
      (node (ref "U1") (pin "46") (pinfunction "PE15_46") (pintype "bidirectional"))
    )
    (net (code "178") (name "unconnected-(U4-IN2-Pad3)") (class "Default")
      (node (ref "U4") (pin "3") (pinfunction "IN2_3") (pintype "input"))
    )
    (net (code "179") (name "unconnected-(U4-OUT2-Pad4)") (class "Default")
      (node (ref "U4") (pin "4") (pinfunction "OUT2_4") (pintype "output"))
    )
    (net (code "180") (name "unconnected-(U5-4A-Pad9)") (class "Default")
      (node (ref "U5") (pin "9") (pinfunction "4A_9") (pintype "bidirectional"))
    )
    (net (code "181") (name "unconnected-(U5-4Y-Pad10)") (class "Default")
      (node (ref "U5") (pin "10") (pinfunction "4Y_10") (pintype "bidirectional"))
    )
    (net (code "182") (name "unconnected-(U5-5A-Pad11)") (class "Default")
      (node (ref "U5") (pin "11") (pinfunction "5A_11") (pintype "bidirectional"))
    )
    (net (code "183") (name "unconnected-(U5-5Y-Pad12)") (class "Default")
      (node (ref "U5") (pin "12") (pinfunction "5Y_12") (pintype "bidirectional"))
    )
    (net (code "184") (name "unconnected-(U5-6A-Pad14)") (class "Default")
      (node (ref "U5") (pin "14") (pinfunction "6A_14") (pintype "bidirectional"))
    )
    (net (code "185") (name "unconnected-(U5-6Y-Pad15)") (class "Default")
      (node (ref "U5") (pin "15") (pinfunction "6Y_15") (pintype "bidirectional"))
    )
  )
)
